# electronGPS.net
KiCad netlist of a schematic drawn in EAGLE
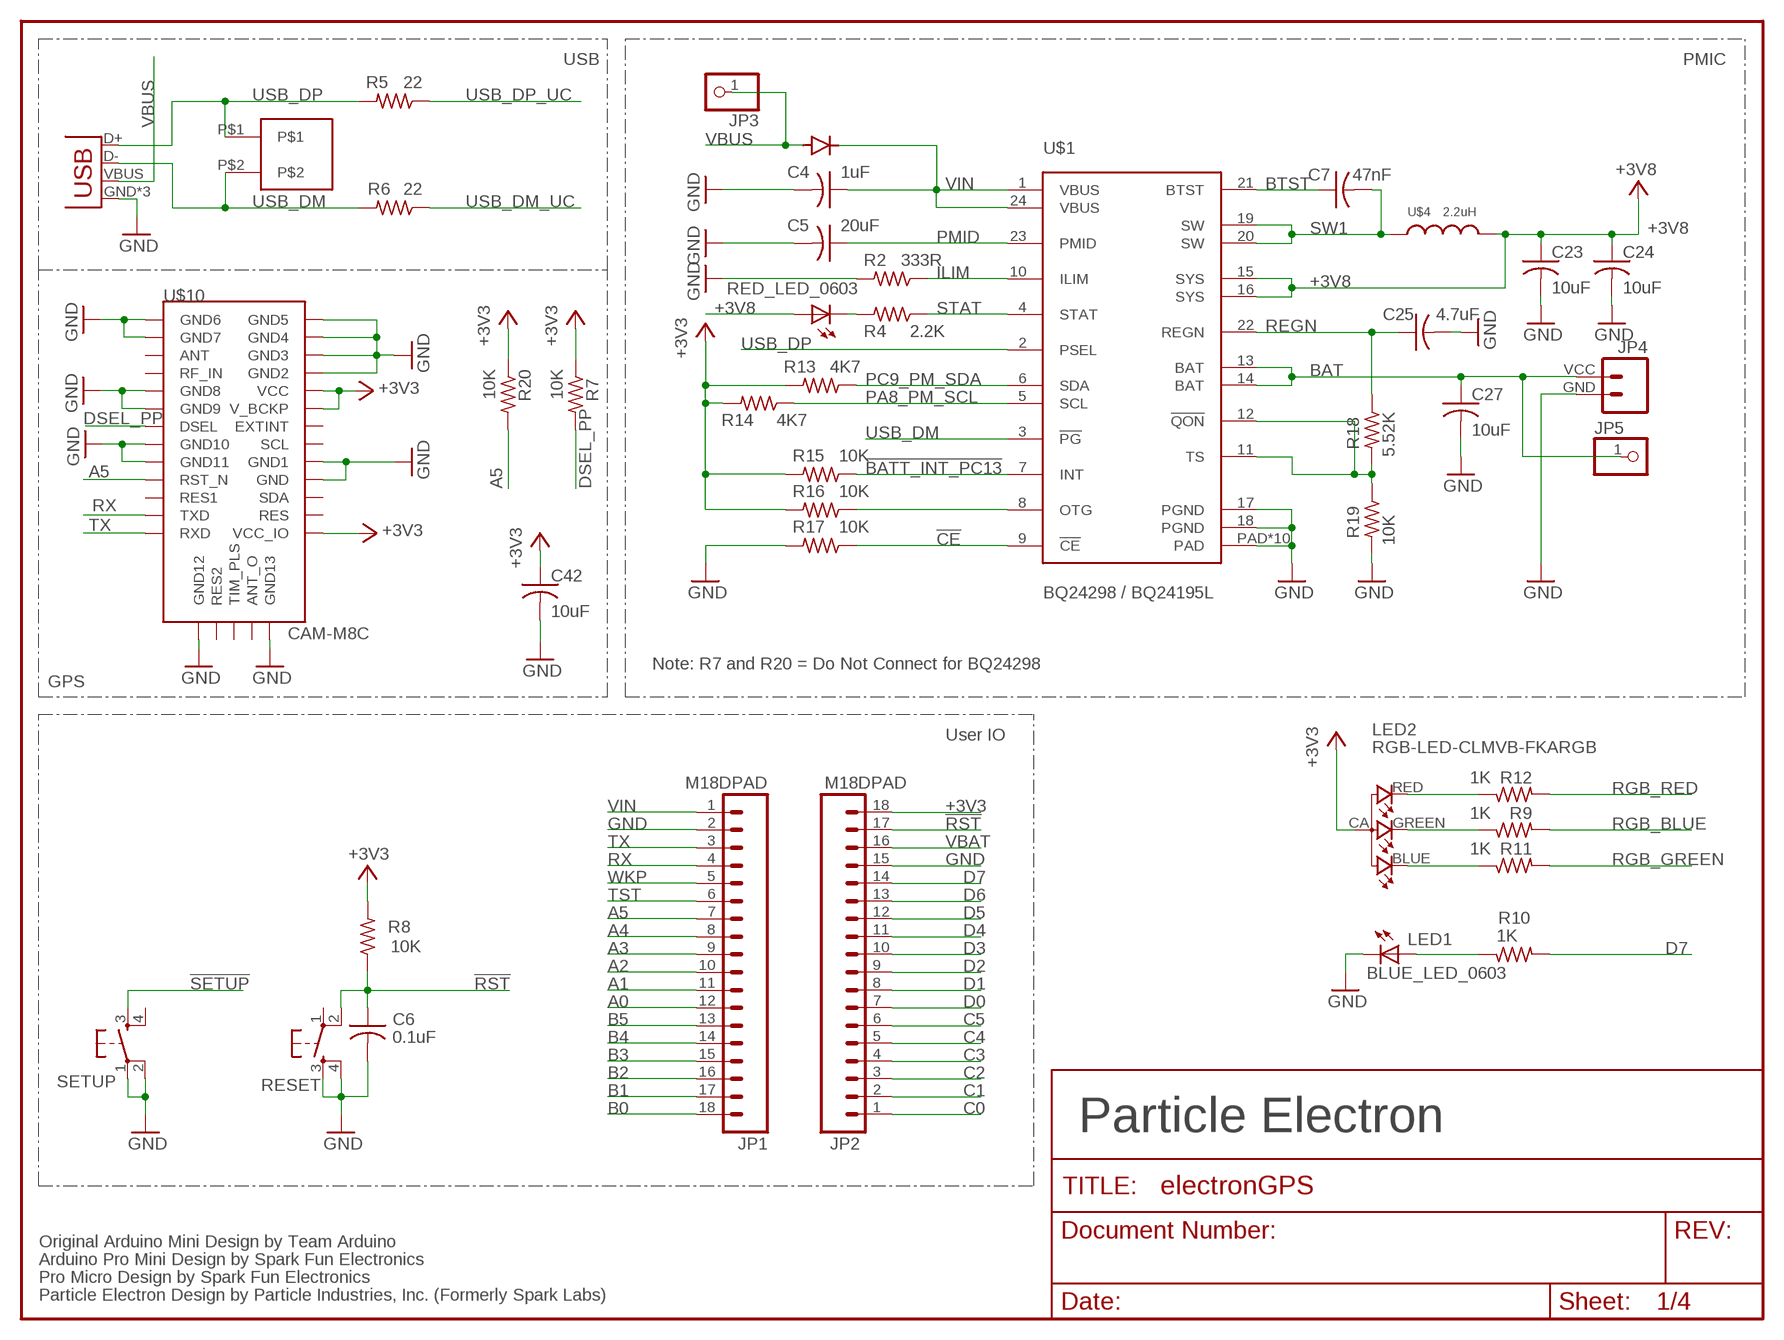
[diagram p0: schematic, sheet 1]
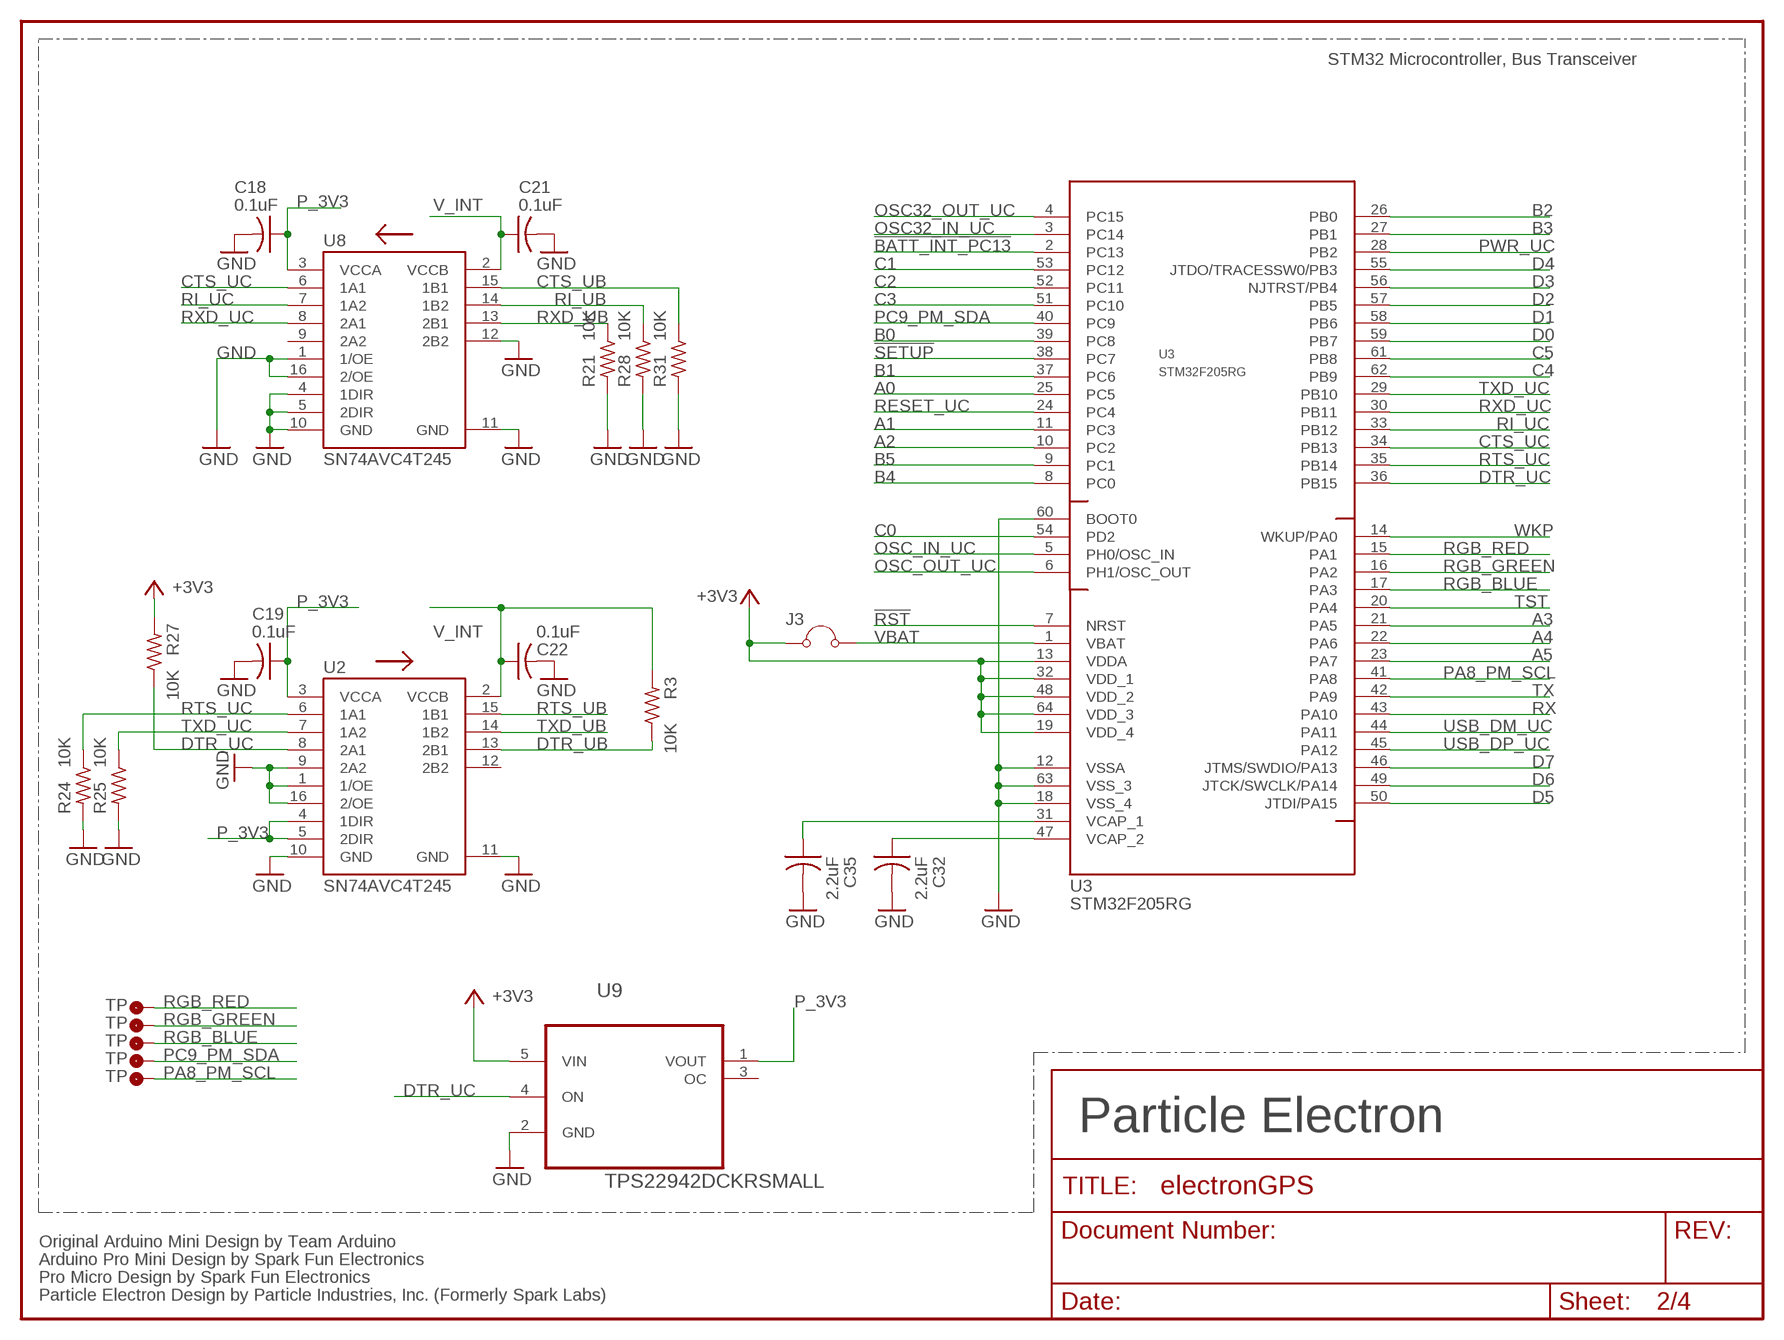
[diagram p1: schematic, sheet 2]
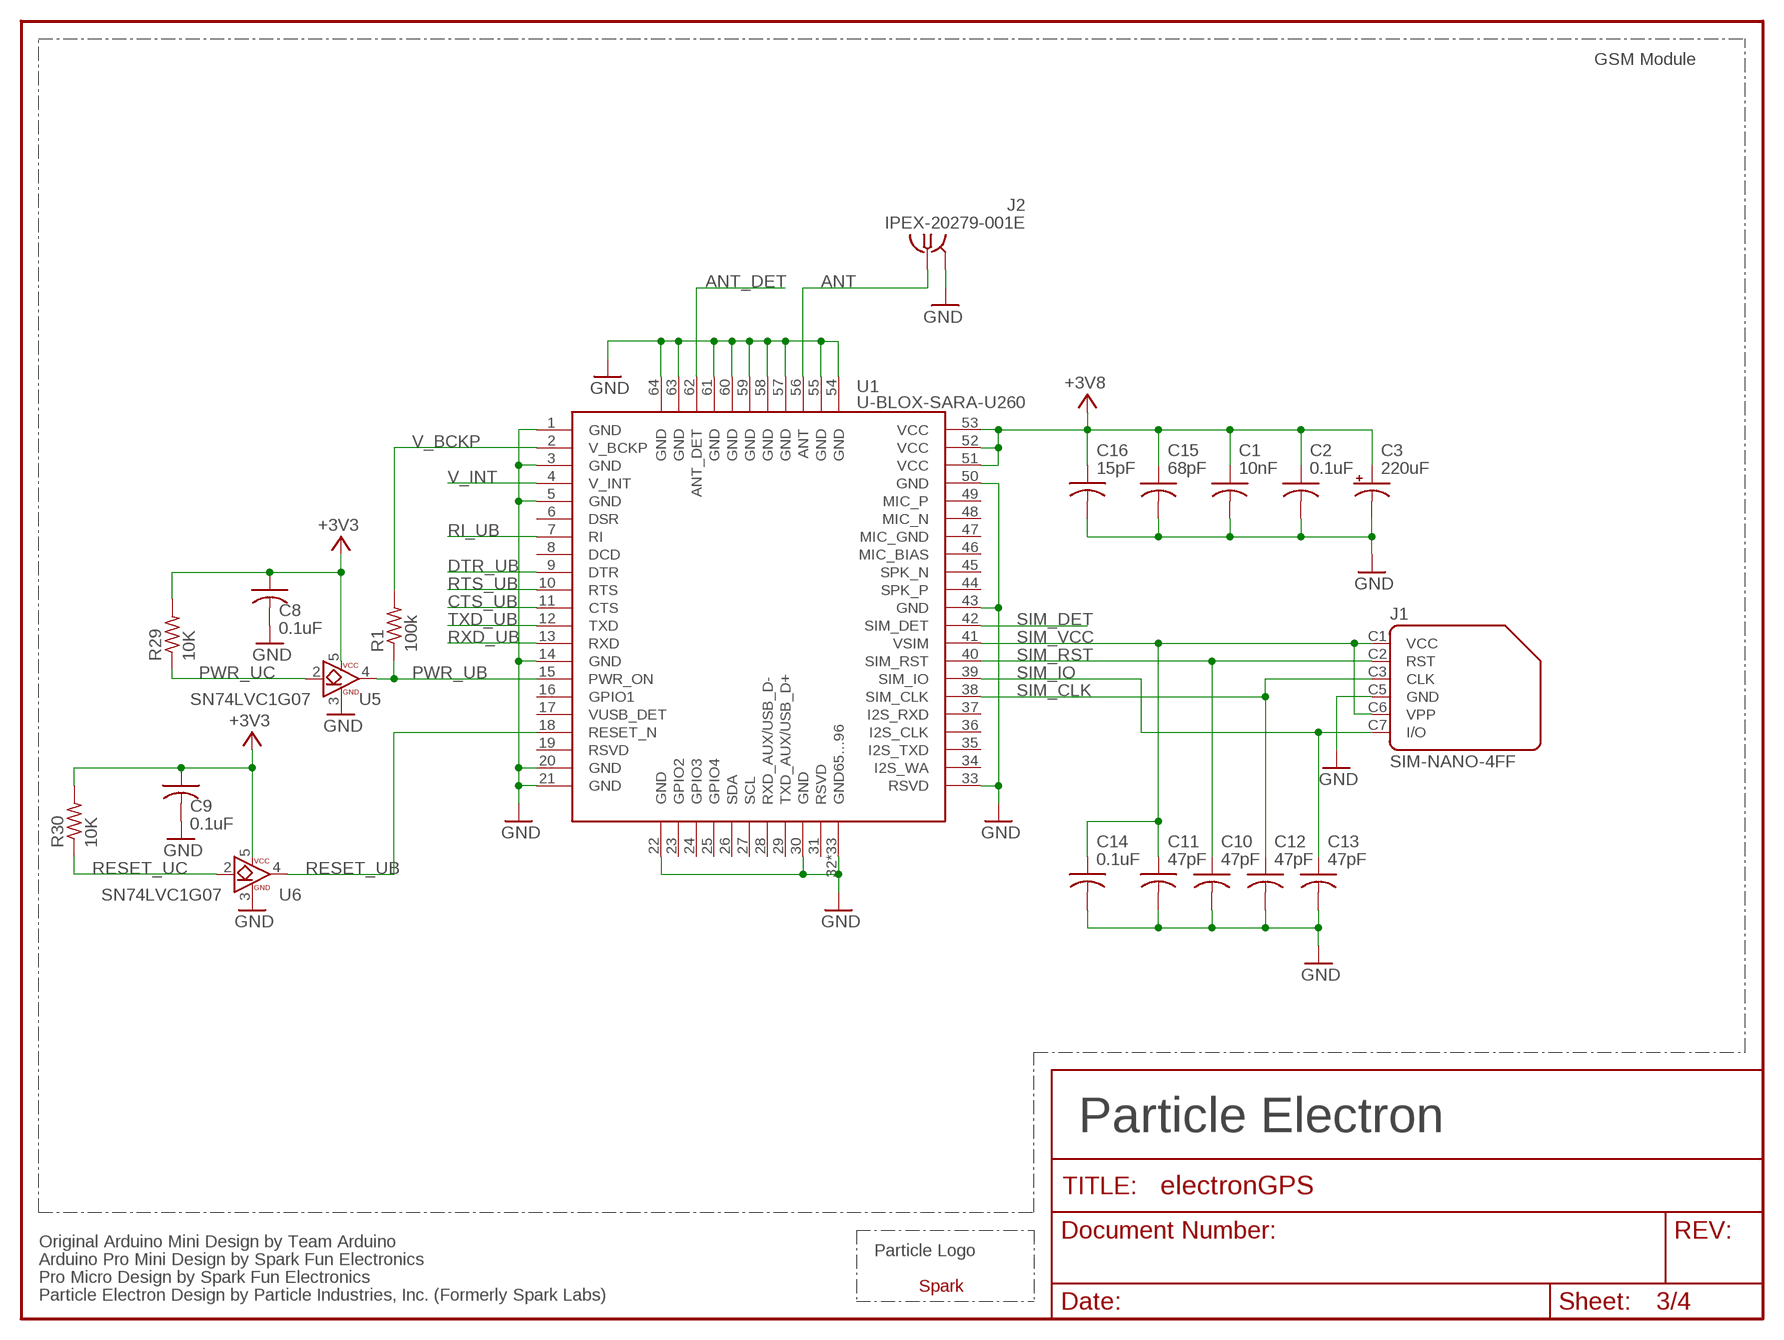
[diagram p2: schematic, sheet 3]
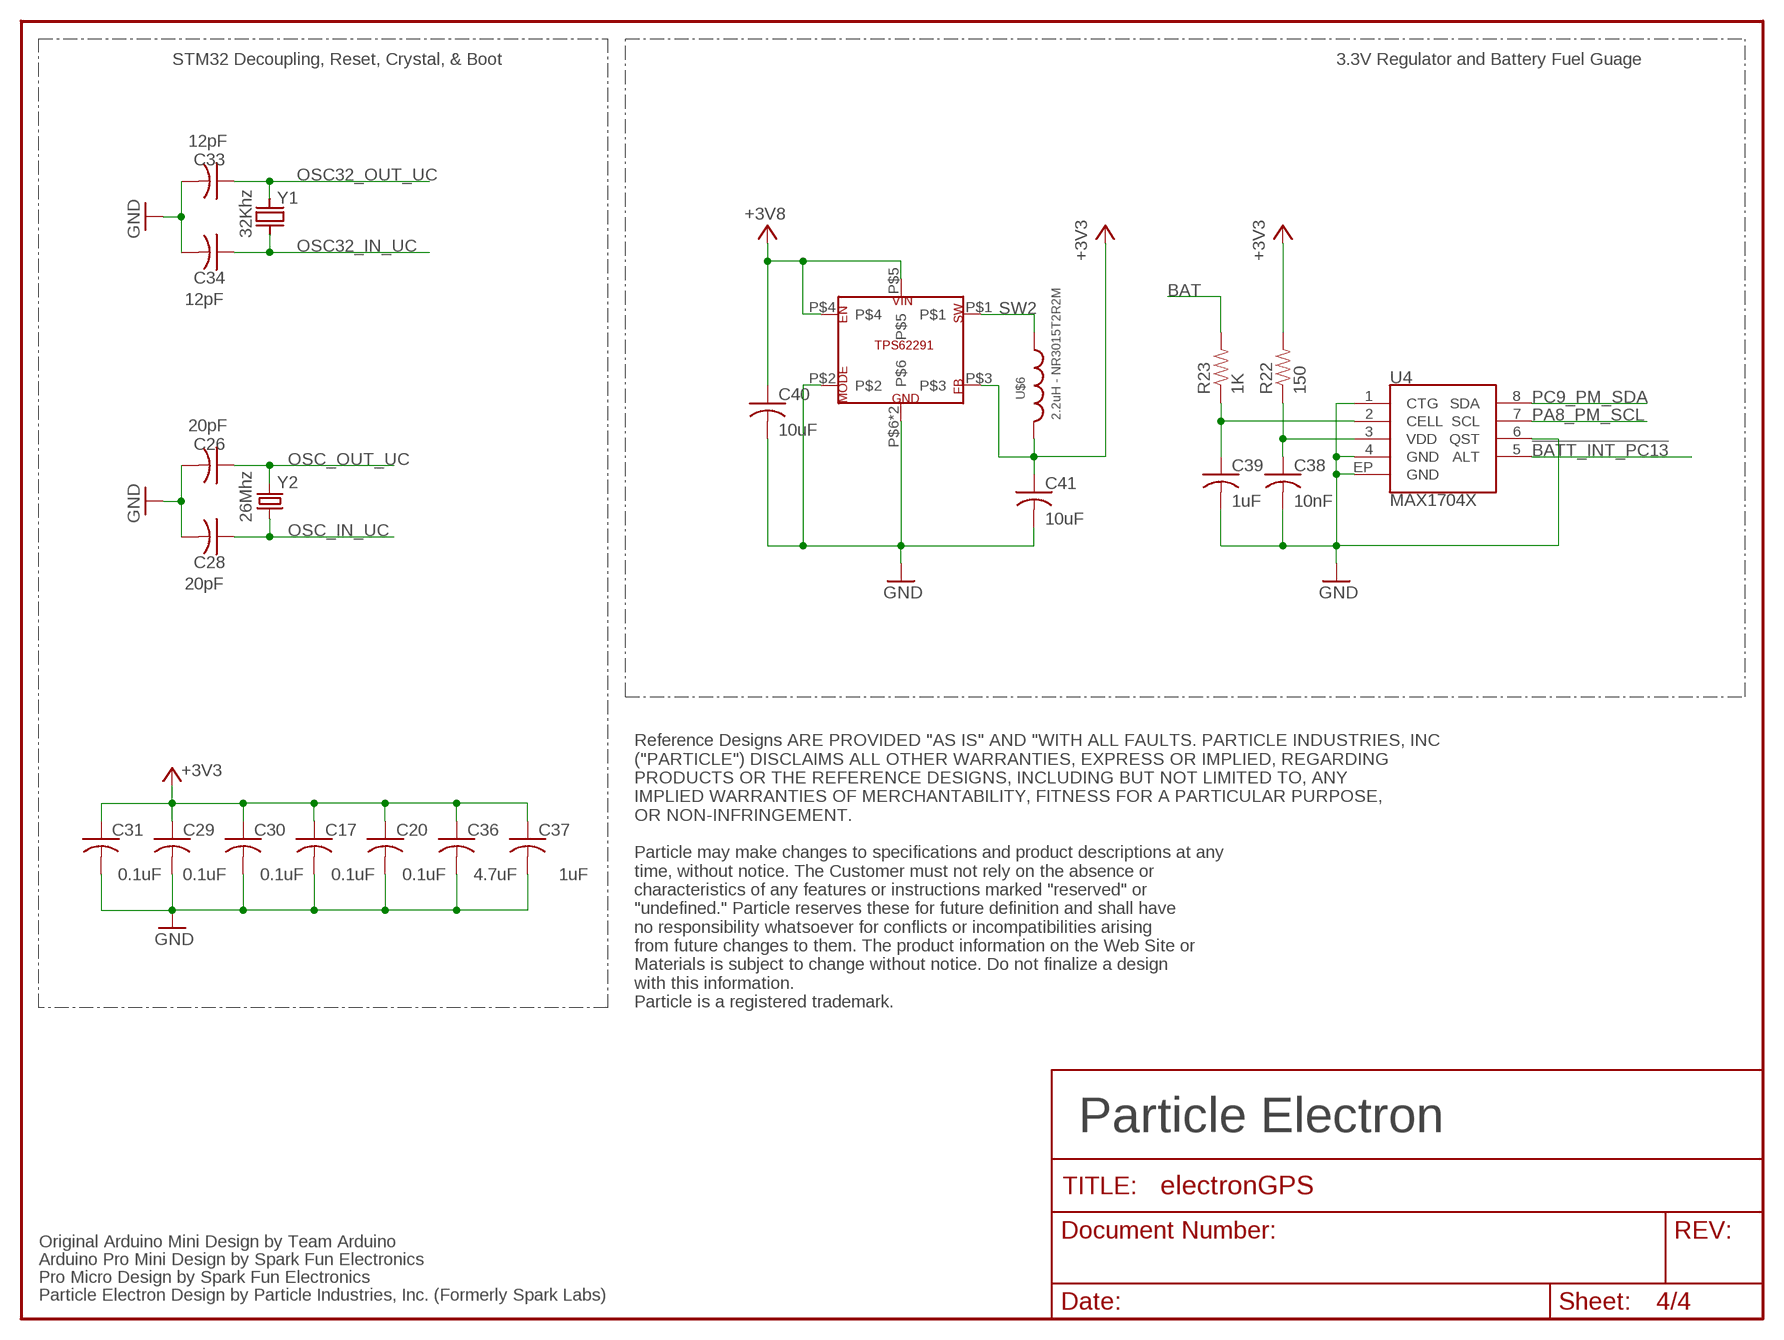
[diagram p3: schematic, sheet 4]

(export (version "E")
  (design (tool "Eeschema 10.0.6"))
  (components
    (comp (ref "C18")
      (value "0.1uF")
      (footprint "eagle-import:C0402_B")
      (libsource (lib "eagle-import") (part "C-US"))
    )
    (comp (ref "C19")
      (value "0.1uF")
      (footprint "eagle-import:C0402_B")
      (libsource (lib "eagle-import") (part "C-US"))
    )
    (comp (ref "C21")
      (value "0.1uF")
      (footprint "eagle-import:C0402_B")
      (libsource (lib "eagle-import") (part "C-US"))
    )
    (comp (ref "C22")
      (value "0.1uF")
      (footprint "eagle-import:C0402_B")
      (libsource (lib "eagle-import") (part "C-US"))
    )
    (comp (ref "C32")
      (value "2.2uF")
      (footprint "eagle-import:C0402_B")
      (libsource (lib "eagle-import") (part "C-US"))
    )
    (comp (ref "C35")
      (value "2.2uF")
      (footprint "eagle-import:C0402_B")
      (libsource (lib "eagle-import") (part "C-US"))
    )
    (comp (ref "J3")
      (value "JUMPER_NC_SMD")
      (footprint "eagle-import:JUMPER_SMD_NC")
      (libsource (lib "eagle-import") (part "JUMPER_NC_SMD"))
    )
    (comp (ref "R3")
      (value "10K")
      (footprint "eagle-import:R0402_B")
      (libsource (lib "eagle-import") (part "R-US_"))
    )
    (comp (ref "R21")
      (value "10K")
      (footprint "eagle-import:R0402_B")
      (libsource (lib "eagle-import") (part "R-US_"))
    )
    (comp (ref "R24")
      (value "10K")
      (footprint "eagle-import:R0402_B")
      (libsource (lib "eagle-import") (part "R-US_"))
    )
    (comp (ref "R25")
      (value "10K")
      (footprint "eagle-import:R0402_B")
      (libsource (lib "eagle-import") (part "R-US_"))
    )
    (comp (ref "R27")
      (value "10K")
      (footprint "eagle-import:R0402_B")
      (libsource (lib "eagle-import") (part "R-US_"))
    )
    (comp (ref "R28")
      (value "10K")
      (footprint "eagle-import:R0402_B")
      (libsource (lib "eagle-import") (part "R-US_"))
    )
    (comp (ref "R31")
      (value "10K")
      (footprint "eagle-import:R0402_B")
      (libsource (lib "eagle-import") (part "R-US_"))
    )
    (comp (ref "U$8")
      (value "TP0")
      (footprint "eagle-import:TP30_BOT")
      (libsource (lib "eagle-import") (part "TP0"))
    )
    (comp (ref "U$9")
      (value "TP0")
      (footprint "eagle-import:TP30_BOT")
      (libsource (lib "eagle-import") (part "TP0"))
    )
    (comp (ref "U$11")
      (value "TP0")
      (footprint "eagle-import:TP30_BOT")
      (libsource (lib "eagle-import") (part "TP0"))
    )
    (comp (ref "U$12")
      (value "TP0")
      (footprint "eagle-import:TP30_BOT")
      (libsource (lib "eagle-import") (part "TP0"))
    )
    (comp (ref "U$13")
      (value "TP0")
      (footprint "eagle-import:TP30_BOT")
      (libsource (lib "eagle-import") (part "TP0"))
    )
    (comp (ref "U2")
      (value "SN74AVC4T245")
      (footprint "eagle-import:UFQFN-16")
      (libsource (lib "eagle-import") (part "SN74AVC4T245"))
    )
    (comp (ref "U3")
      (value "STM32F205RG")
      (footprint "eagle-import:LQFP64")
      (libsource (lib "eagle-import") (part "STM32F20XR"))
    )
    (comp (ref "U8")
      (value "SN74AVC4T245")
      (footprint "eagle-import:UFQFN-16")
      (libsource (lib "eagle-import") (part "SN74AVC4T245"))
    )
    (comp (ref "U9")
      (value "TPS22942DCKRSMALL")
      (footprint "eagle-import:SC70-5")
      (libsource (lib "eagle-import") (part "TPS22942DCKRSMALL"))
    )
    (comp (ref "BLUE_LED_0603")
      (value "LEDNOSILK")
      (footprint "eagle-import:LED-0603-NS")
      (libsource (lib "eagle-import") (part "LEDNOSILK"))
    )
    (comp (ref "C4")
      (value "1uF")
      (footprint "eagle-import:C0603_B")
      (libsource (lib "eagle-import") (part "C-US0603"))
    )
    (comp (ref "C5")
      (value "20uF")
      (footprint "eagle-import:C0603_B")
      (libsource (lib "eagle-import") (part "C-US0603"))
    )
    (comp (ref "C6")
      (value "0.1uF")
      (footprint "eagle-import:C0402_B")
      (libsource (lib "eagle-import") (part "C-US"))
    )
    (comp (ref "C7")
      (value "47nF")
      (footprint "eagle-import:C0402_B")
      (libsource (lib "eagle-import") (part "C-US"))
    )
    (comp (ref "C23")
      (value "10uF")
      (footprint "eagle-import:C0603_B")
      (libsource (lib "eagle-import") (part "C-US0603"))
    )
    (comp (ref "C24")
      (value "10uF")
      (footprint "eagle-import:C0603_B")
      (libsource (lib "eagle-import") (part "C-US0603"))
    )
    (comp (ref "C25")
      (value "4.7uF")
      (footprint "eagle-import:C0603_B")
      (libsource (lib "eagle-import") (part "C-US0603"))
    )
    (comp (ref "C27")
      (value "10uF")
      (footprint "eagle-import:C0603_B")
      (libsource (lib "eagle-import") (part "C-US0603"))
    )
    (comp (ref "C42")
      (value "10uF")
      (footprint "eagle-import:C0603_B")
      (libsource (lib "eagle-import") (part "C-US0603"))
    )
    (comp (ref "JP1")
      (value "M18DPAD")
      (footprint "eagle-import:1X18-D-PADS")
      (libsource (lib "eagle-import") (part "M18DPAD"))
    )
    (comp (ref "JP2")
      (value "M18DPAD")
      (footprint "eagle-import:1X18-D-PADS")
      (libsource (lib "eagle-import") (part "M18DPAD"))
    )
    (comp (ref "JP3")
      (value "PINHD-1X1NOSILK")
      (footprint "eagle-import:1X01_NO_SILK")
      (libsource (lib "eagle-import") (part "PINHD-1X1NOSILK"))
    )
    (comp (ref "JP4")
      (value "M024UCON-15767")
      (footprint "eagle-import:JST-2-SMD-VERT")
      (libsource (lib "eagle-import") (part "M024UCON-15767"))
    )
    (comp (ref "JP5")
      (value "PINHD-1X1NOSILK")
      (footprint "eagle-import:1X01_NO_SILK")
      (libsource (lib "eagle-import") (part "PINHD-1X1NOSILK"))
    )
    (comp (ref "LED2")
      (value "RGB-LED-CLMVB-FKARGB")
      (footprint "eagle-import:PLCC4-2MM-RGB")
      (libsource (lib "eagle-import") (part "RGB-LED-CLMVB-FKARGB"))
    )
    (comp (ref "R2")
      (value "333R")
      (footprint "eagle-import:R0402_B")
      (libsource (lib "eagle-import") (part "R-US_"))
    )
    (comp (ref "R4")
      (value "2.2K")
      (footprint "eagle-import:R0402_B")
      (libsource (lib "eagle-import") (part "R-US_"))
    )
    (comp (ref "R5")
      (value "22")
      (footprint "eagle-import:R0402_B")
      (libsource (lib "eagle-import") (part "R-US_"))
    )
    (comp (ref "R6")
      (value "22")
      (footprint "eagle-import:R0402_B")
      (libsource (lib "eagle-import") (part "R-US_"))
    )
    (comp (ref "R7")
      (value "10K")
      (footprint "eagle-import:R0402_B")
      (libsource (lib "eagle-import") (part "R-US_"))
    )
    (comp (ref "R8")
      (value "10K")
      (footprint "eagle-import:R0402_B")
      (libsource (lib "eagle-import") (part "R-US_"))
    )
    (comp (ref "R9")
      (value "1K")
      (footprint "eagle-import:R0402_B")
      (libsource (lib "eagle-import") (part "R-US_"))
    )
    (comp (ref "R10")
      (value "1K")
      (footprint "eagle-import:R0402_B")
      (libsource (lib "eagle-import") (part "R-US_"))
    )
    (comp (ref "R11")
      (value "1K")
      (footprint "eagle-import:R0402_B")
      (libsource (lib "eagle-import") (part "R-US_"))
    )
    (comp (ref "R12")
      (value "1K")
      (footprint "eagle-import:R0402_B")
      (libsource (lib "eagle-import") (part "R-US_"))
    )
    (comp (ref "R13")
      (value "4K7")
      (footprint "eagle-import:R0402_B")
      (libsource (lib "eagle-import") (part "R-US_"))
    )
    (comp (ref "R14")
      (value "4K7")
      (footprint "eagle-import:R0402_B")
      (libsource (lib "eagle-import") (part "R-US_"))
    )
    (comp (ref "R15")
      (value "10K")
      (footprint "eagle-import:R0402_B")
      (libsource (lib "eagle-import") (part "R-US_"))
    )
    (comp (ref "R16")
      (value "10K")
      (footprint "eagle-import:R0402_B")
      (libsource (lib "eagle-import") (part "R-US_"))
    )
    (comp (ref "R17")
      (value "10K")
      (footprint "eagle-import:R0402_B")
      (libsource (lib "eagle-import") (part "R-US_"))
    )
    (comp (ref "R18")
      (value "5.52K")
      (footprint "eagle-import:R0402_B")
      (libsource (lib "eagle-import") (part "R-US_"))
    )
    (comp (ref "R19")
      (value "10K")
      (footprint "eagle-import:R0402_B")
      (libsource (lib "eagle-import") (part "R-US_"))
    )
    (comp (ref "R20")
      (value "10K")
      (footprint "eagle-import:R0402_B")
      (libsource (lib "eagle-import") (part "R-US_"))
    )
    (comp (ref "RED_LED_0603")
      (value "LED0603")
      (footprint "eagle-import:LED-0603")
      (libsource (lib "eagle-import") (part "LED0603"))
    )
    (comp (ref "RESET")
      (value "KMR211GLFS")
      (footprint "eagle-import:TACTILE_SWITCH_SMD")
      (libsource (lib "eagle-import") (part "TAC_SWITCHSMD"))
    )
    (comp (ref "SETUP")
      (value "KMR211GLFS")
      (footprint "eagle-import:TACTILE_SWITCH_SMD")
      (libsource (lib "eagle-import") (part "TAC_SWITCHSMD"))
    )
    (comp (ref "U$1")
      (value "BQ24298 / BQ24195L")
      (footprint "eagle-import:QFN24")
      (libsource (lib "eagle-import") (part "BQ24298RTWR"))
    )
    (comp (ref "U$3")
      (value "DIODE_NT")
      (footprint "eagle-import:DIODE-DO-220AA_NT(SMP)")
      (libsource (lib "eagle-import") (part "DIODE_NT"))
    )
    (comp (ref "U$4")
      (value "2.2uH")
      (footprint "eagle-import:4020TYPE_NT")
      (libsource (lib "eagle-import") (part "INDUCTOR_NT"))
    )
    (comp (ref "U$7")
      (value "M02_0.05_HEADER")
      (footprint "eagle-import:M02_0.05_HEADER")
      (libsource (lib "eagle-import") (part "M02_0.05_HEADER"))
    )
    (comp (ref "U$10")
      (value "CAM-M8C")
      (footprint "eagle-import:CAM-MC")
      (libsource (lib "eagle-import") (part "CAM-M8C"))
    )
    (comp (ref "X1")
      (value "USB-MICROB")
      (footprint "eagle-import:USB-MICROB-SLOT-HOLE")
      (libsource (lib "eagle-import") (part "USBUSB-MICROB-SLOT-HOLE"))
    )
    (comp (ref "C1")
      (value "10nF")
      (footprint "eagle-import:C0402_B")
      (libsource (lib "eagle-import") (part "C-US"))
    )
    (comp (ref "C2")
      (value "0.1uF")
      (footprint "eagle-import:C0402_B")
      (libsource (lib "eagle-import") (part "C-US"))
    )
    (comp (ref "C3")
      (value "220uF")
      (footprint "eagle-import:C_6032-28R")
      (libsource (lib "eagle-import") (part "CPOL-USC/6032-28R"))
    )
    (comp (ref "C8")
      (value "0.1uF")
      (footprint "eagle-import:C0402_B")
      (libsource (lib "eagle-import") (part "C-US"))
    )
    (comp (ref "C9")
      (value "0.1uF")
      (footprint "eagle-import:C0402_B")
      (libsource (lib "eagle-import") (part "C-US"))
    )
    (comp (ref "C10")
      (value "47pF")
      (footprint "eagle-import:C0402_B")
      (libsource (lib "eagle-import") (part "C-US"))
    )
    (comp (ref "C11")
      (value "47pF")
      (footprint "eagle-import:C0402_B")
      (libsource (lib "eagle-import") (part "C-US"))
    )
    (comp (ref "C12")
      (value "47pF")
      (footprint "eagle-import:C0402_B")
      (libsource (lib "eagle-import") (part "C-US"))
    )
    (comp (ref "C13")
      (value "47pF")
      (footprint "eagle-import:C0402_B")
      (libsource (lib "eagle-import") (part "C-US"))
    )
    (comp (ref "C14")
      (value "0.1uF")
      (footprint "eagle-import:C0402_B")
      (libsource (lib "eagle-import") (part "C-US"))
    )
    (comp (ref "C15")
      (value "68pF")
      (footprint "eagle-import:C0402_B")
      (libsource (lib "eagle-import") (part "C-US"))
    )
    (comp (ref "C16")
      (value "15pF")
      (footprint "eagle-import:C0402_B")
      (libsource (lib "eagle-import") (part "C-US"))
    )
    (comp (ref "J1")
      (value "SIM-NANO-4FF")
      (footprint "eagle-import:GCT-SIM8100")
      (libsource (lib "eagle-import") (part "SIM-NANO-4FF"))
    )
    (comp (ref "J2")
      (value "IPEX-20279-001E")
      (footprint "eagle-import:IPEX-20279-001E")
      (libsource (lib "eagle-import") (part "IPEX-20279-001E"))
    )
    (comp (ref "R1")
      (value "100k")
      (footprint "eagle-import:R0402_B")
      (libsource (lib "eagle-import") (part "R-US_"))
    )
    (comp (ref "R29")
      (value "10K")
      (footprint "eagle-import:R0402_B")
      (libsource (lib "eagle-import") (part "R-US_"))
    )
    (comp (ref "R30")
      (value "10K")
      (footprint "eagle-import:R0402_B")
      (libsource (lib "eagle-import") (part "R-US_"))
    )
    (comp (ref "U$2")
      (value "SPARK_LOGO2")
      (footprint "eagle-import:SPARK_LOGO2")
      (libsource (lib "eagle-import") (part "SPARK_LOGO2"))
    )
    (comp (ref "U1")
      (value "U-BLOX-SARA-U260")
      (footprint "eagle-import:U-BLOX-SARA-U2")
      (libsource (lib "eagle-import") (part "U-BLOX-SARA-U260"))
    )
    (comp (ref "U5")
      (value "SN74LVC1G07")
      (footprint "eagle-import:SC-70-5")
      (libsource (lib "eagle-import") (part "SN74LVC1G07"))
    )
    (comp (ref "U6")
      (value "SN74LVC1G07")
      (footprint "eagle-import:SC-70-5")
      (libsource (lib "eagle-import") (part "SN74LVC1G07"))
    )
    (comp (ref "C17")
      (value "0.1uF")
      (footprint "eagle-import:C0402_B")
      (libsource (lib "eagle-import") (part "C-US"))
    )
    (comp (ref "C20")
      (value "0.1uF")
      (footprint "eagle-import:C0402_B")
      (libsource (lib "eagle-import") (part "C-US"))
    )
    (comp (ref "C26")
      (value "20pF")
      (footprint "eagle-import:C0402_B")
      (libsource (lib "eagle-import") (part "C-US"))
    )
    (comp (ref "C28")
      (value "20pF")
      (footprint "eagle-import:C0402_B")
      (libsource (lib "eagle-import") (part "C-US"))
    )
    (comp (ref "C29")
      (value "0.1uF")
      (footprint "eagle-import:C0402_B")
      (libsource (lib "eagle-import") (part "C-US"))
    )
    (comp (ref "C30")
      (value "0.1uF")
      (footprint "eagle-import:C0402_B")
      (libsource (lib "eagle-import") (part "C-US"))
    )
    (comp (ref "C31")
      (value "0.1uF")
      (footprint "eagle-import:C0402_B")
      (libsource (lib "eagle-import") (part "C-US"))
    )
    (comp (ref "C33")
      (value "12pF")
      (footprint "eagle-import:C0402_B")
      (libsource (lib "eagle-import") (part "C-US"))
    )
    (comp (ref "C34")
      (value "12pF")
      (footprint "eagle-import:C0402_B")
      (libsource (lib "eagle-import") (part "C-US"))
    )
    (comp (ref "C36")
      (value "4.7uF")
      (footprint "eagle-import:C0402_B")
      (libsource (lib "eagle-import") (part "C-US"))
    )
    (comp (ref "C37")
      (value "1uF")
      (footprint "eagle-import:C0402_B")
      (libsource (lib "eagle-import") (part "C-US"))
    )
    (comp (ref "C38")
      (value "10nF")
      (footprint "eagle-import:C0402_B")
      (libsource (lib "eagle-import") (part "C-US"))
    )
    (comp (ref "C39")
      (value "1uF")
      (footprint "eagle-import:C0402_B")
      (libsource (lib "eagle-import") (part "C-US"))
    )
    (comp (ref "C40")
      (value "10uF")
      (footprint "eagle-import:C0603_B")
      (libsource (lib "eagle-import") (part "C-US0603"))
    )
    (comp (ref "C41")
      (value "10uF")
      (footprint "eagle-import:C0603_B")
      (libsource (lib "eagle-import") (part "C-US0603"))
    )
    (comp (ref "R22")
      (value "150")
      (footprint "eagle-import:0603-RES")
      (libsource (lib "eagle-import") (part "RESISTOR0603-RES"))
    )
    (comp (ref "R23")
      (value "1K")
      (footprint "eagle-import:0603-RES")
      (libsource (lib "eagle-import") (part "RESISTOR0603-RES"))
    )
    (comp (ref "U$5")
      (value "TPS62291DRV")
      (footprint "eagle-import:S-PWSON-N6")
      (libsource (lib "eagle-import") (part "TPS62291DRV"))
    )
    (comp (ref "U$6")
      (value "2.2uH - NR3015T2R2M")
      (footprint "eagle-import:INDUCTOR-NR3015")
      (libsource (lib "eagle-import") (part "INDUCTORB"))
    )
    (comp (ref "U4")
      (value "MAX1704X")
      (footprint "eagle-import:TDFN-8")
      (libsource (lib "eagle-import") (part "MAX1704X"))
    )
    (comp (ref "Y1")
      (value "32Khz")
      (footprint "eagle-import:FC135")
      (libsource (lib "eagle-import") (part "Q_FC135"))
    )
    (comp (ref "Y2")
      (value "26Mhz")
      (footprint "eagle-import:CRYSTAL-SMD-5X3")
      (libsource (lib "eagle-import") (part "CRYSTAL5X3"))
    )
  )
  (nets
    (net (code "1") (name "+3V3") (class "Default")
      (node (ref "C17") (pin "1") (pinfunction "1_1") (pintype "passive"))
      (node (ref "C20") (pin "1") (pinfunction "1_1") (pintype "passive"))
      (node (ref "C29") (pin "1") (pinfunction "1_1") (pintype "passive"))
      (node (ref "C30") (pin "1") (pinfunction "1_1") (pintype "passive"))
      (node (ref "C31") (pin "1") (pinfunction "1_1") (pintype "passive"))
      (node (ref "C36") (pin "1") (pinfunction "1_1") (pintype "passive"))
      (node (ref "C37") (pin "1") (pinfunction "1_1") (pintype "passive"))
      (node (ref "C41") (pin "1") (pinfunction "1_1") (pintype "passive"))
      (node (ref "C42") (pin "1") (pinfunction "1_1") (pintype "passive"))
      (node (ref "C8") (pin "1") (pinfunction "1_1") (pintype "passive"))
      (node (ref "C9") (pin "1") (pinfunction "1_1") (pintype "passive"))
      (node (ref "J3") (pin "1") (pinfunction "1_1") (pintype "bidirectional"))
      (node (ref "JP2") (pin "18") (pinfunction "18_18") (pintype "passive"))
      (node (ref "LED2") (pin "CA") (pinfunction "1_CA") (pintype "passive"))
      (node (ref "R13") (pin "2") (pinfunction "2_2") (pintype "passive"))
      (node (ref "R14") (pin "2") (pinfunction "2_2") (pintype "passive"))
      (node (ref "R15") (pin "2") (pinfunction "2_2") (pintype "passive"))
      (node (ref "R16") (pin "2") (pinfunction "2_2") (pintype "passive"))
      (node (ref "R20") (pin "1") (pinfunction "1_1") (pintype "passive"))
      (node (ref "R22") (pin "2") (pinfunction "2_2") (pintype "passive"))
      (node (ref "R27") (pin "2") (pinfunction "2_2") (pintype "passive"))
      (node (ref "R29") (pin "2") (pinfunction "2_2") (pintype "passive"))
      (node (ref "R30") (pin "2") (pinfunction "2_2") (pintype "passive"))
      (node (ref "R7") (pin "1") (pinfunction "1_1") (pintype "passive"))
      (node (ref "R8") (pin "2") (pinfunction "2_2") (pintype "passive"))
      (node (ref "U$10") (pin "P$1") (pinfunction "VCC_IO_P$1") (pintype "bidirectional"))
      (node (ref "U$10") (pin "P$8") (pinfunction "V_BCKP_P$8") (pintype "bidirectional"))
      (node (ref "U$10") (pin "P$9") (pinfunction "VCC_P$9") (pintype "bidirectional"))
      (node (ref "U$5") (pin "P$3") (pinfunction "P$3_P$3") (pintype "bidirectional"))
      (node (ref "U$6") (pin "2") (pinfunction "2_2") (pintype "passive"))
      (node (ref "U3") (pin "13") (pinfunction "VDDA_13") (pintype "power_in"))
      (node (ref "U3") (pin "19") (pinfunction "VDD_4_19") (pintype "power_in"))
      (node (ref "U3") (pin "32") (pinfunction "VDD_1_32") (pintype "power_in"))
      (node (ref "U3") (pin "48") (pinfunction "VDD_2_48") (pintype "power_in"))
      (node (ref "U3") (pin "64") (pinfunction "VDD_3_64") (pintype "power_in"))
      (node (ref "U5") (pin "5") (pinfunction "VCC_5") (pintype "bidirectional"))
      (node (ref "U6") (pin "5") (pinfunction "VCC_5") (pintype "bidirectional"))
      (node (ref "U9") (pin "5") (pinfunction "VIN_5") (pintype "power_in"))
    )
    (net (code "2") (name "+3V8") (class "Default")
      (node (ref "C1") (pin "1") (pinfunction "1_1") (pintype "passive"))
      (node (ref "C15") (pin "1") (pinfunction "1_1") (pintype "passive"))
      (node (ref "C16") (pin "1") (pinfunction "1_1") (pintype "passive"))
      (node (ref "C2") (pin "1") (pinfunction "1_1") (pintype "passive"))
      (node (ref "C23") (pin "1") (pinfunction "1_1") (pintype "passive"))
      (node (ref "C24") (pin "1") (pinfunction "1_1") (pintype "passive"))
      (node (ref "C3") (pin "+") (pinfunction "+_+") (pintype "passive"))
      (node (ref "C40") (pin "1") (pinfunction "1_1") (pintype "passive"))
      (node (ref "RED_LED_0603") (pin "A") (pinfunction "A_A") (pintype "passive"))
      (node (ref "U$1") (pin "15") (pinfunction "SYS_15") (pintype "power_in"))
      (node (ref "U$1") (pin "16") (pinfunction "SYS_16") (pintype "power_in"))
      (node (ref "U$4") (pin "P$2") (pinfunction "2_P$2") (pintype "passive"))
      (node (ref "U$5") (pin "P$4") (pinfunction "P$4_P$4") (pintype "bidirectional"))
      (node (ref "U$5") (pin "P$5") (pinfunction "P$5_P$5") (pintype "bidirectional"))
      (node (ref "U1") (pin "51") (pinfunction "VCC_51") (pintype "bidirectional"))
      (node (ref "U1") (pin "52") (pinfunction "VCC_52") (pintype "bidirectional"))
      (node (ref "U1") (pin "53") (pinfunction "VCC_53") (pintype "bidirectional"))
    )
    (net (code "3") (name "A0") (class "Default")
      (node (ref "JP1") (pin "12") (pinfunction "12_12") (pintype "passive"))
      (node (ref "U3") (pin "25") (pinfunction "PC5_25") (pintype "bidirectional"))
    )
    (net (code "4") (name "A1") (class "Default")
      (node (ref "JP1") (pin "11") (pinfunction "11_11") (pintype "passive"))
      (node (ref "U3") (pin "11") (pinfunction "PC3_11") (pintype "bidirectional"))
    )
    (net (code "5") (name "A2") (class "Default")
      (node (ref "JP1") (pin "10") (pinfunction "10_10") (pintype "passive"))
      (node (ref "U3") (pin "10") (pinfunction "PC2_10") (pintype "bidirectional"))
    )
    (net (code "6") (name "A3") (class "Default")
      (node (ref "JP1") (pin "9") (pinfunction "9_9") (pintype "passive"))
      (node (ref "U3") (pin "21") (pinfunction "PA5_21") (pintype "bidirectional"))
    )
    (net (code "7") (name "A4") (class "Default")
      (node (ref "JP1") (pin "8") (pinfunction "8_8") (pintype "passive"))
      (node (ref "U3") (pin "22") (pinfunction "PA6_22") (pintype "bidirectional"))
    )
    (net (code "8") (name "A5") (class "Default")
      (node (ref "JP1") (pin "7") (pinfunction "7_7") (pintype "passive"))
      (node (ref "R20") (pin "2") (pinfunction "2_2") (pintype "passive"))
      (node (ref "U$10") (pin "P$23") (pinfunction "RST_N_P$23") (pintype "bidirectional"))
      (node (ref "U3") (pin "23") (pinfunction "PA7_23") (pintype "bidirectional"))
    )
    (net (code "9") (name "ANT") (class "Default")
      (node (ref "J2") (pin "1") (pinfunction "1_1") (pintype "passive"))
      (node (ref "U1") (pin "56") (pinfunction "ANT_56") (pintype "bidirectional"))
    )
    (net (code "10") (name "ANT_DET") (class "Default")
      (node (ref "U1") (pin "62") (pinfunction "ANT_DET_62") (pintype "bidirectional"))
    )
    (net (code "11") (name "B0") (class "Default")
      (node (ref "JP1") (pin "18") (pinfunction "18_18") (pintype "passive"))
      (node (ref "U3") (pin "39") (pinfunction "PC8_39") (pintype "bidirectional"))
    )
    (net (code "12") (name "B1") (class "Default")
      (node (ref "JP1") (pin "17") (pinfunction "17_17") (pintype "passive"))
      (node (ref "U3") (pin "37") (pinfunction "PC6_37") (pintype "bidirectional"))
    )
    (net (code "13") (name "B2") (class "Default")
      (node (ref "JP1") (pin "16") (pinfunction "16_16") (pintype "passive"))
      (node (ref "U3") (pin "26") (pinfunction "PB0_26") (pintype "bidirectional"))
    )
    (net (code "14") (name "B3") (class "Default")
      (node (ref "JP1") (pin "15") (pinfunction "15_15") (pintype "passive"))
      (node (ref "U3") (pin "27") (pinfunction "PB1_27") (pintype "bidirectional"))
    )
    (net (code "15") (name "B4") (class "Default")
      (node (ref "JP1") (pin "14") (pinfunction "14_14") (pintype "passive"))
      (node (ref "U3") (pin "8") (pinfunction "PC0_8") (pintype "bidirectional"))
    )
    (net (code "16") (name "B5") (class "Default")
      (node (ref "JP1") (pin "13") (pinfunction "13_13") (pintype "passive"))
      (node (ref "U3") (pin "9") (pinfunction "PC1_9") (pintype "bidirectional"))
    )
    (net (code "17") (name "BAT") (class "Default")
      (node (ref "C27") (pin "1") (pinfunction "1_1") (pintype "passive"))
      (node (ref "JP4") (pin "VCC") (pinfunction "2_VCC") (pintype "passive"))
      (node (ref "JP5") (pin "1") (pinfunction "1_1") (pintype "passive"))
      (node (ref "R23") (pin "2") (pinfunction "2_2") (pintype "passive"))
      (node (ref "U$1") (pin "13") (pinfunction "BAT_13") (pintype "passive"))
      (node (ref "U$1") (pin "14") (pinfunction "BAT_14") (pintype "power_in"))
    )
    (net (code "18") (name "BTST") (class "Default")
      (node (ref "C7") (pin "1") (pinfunction "1_1") (pintype "passive"))
      (node (ref "U$1") (pin "21") (pinfunction "BTST_21") (pintype "bidirectional"))
    )
    (net (code "19") (name "C0") (class "Default")
      (node (ref "JP2") (pin "1") (pinfunction "1_1") (pintype "passive"))
      (node (ref "U3") (pin "54") (pinfunction "PD2_54") (pintype "bidirectional"))
    )
    (net (code "20") (name "C1") (class "Default")
      (node (ref "JP2") (pin "2") (pinfunction "2_2") (pintype "passive"))
      (node (ref "U3") (pin "53") (pinfunction "PC12_53") (pintype "bidirectional"))
    )
    (net (code "21") (name "C2") (class "Default")
      (node (ref "JP2") (pin "3") (pinfunction "3_3") (pintype "passive"))
      (node (ref "U3") (pin "52") (pinfunction "PC11_52") (pintype "bidirectional"))
    )
    (net (code "22") (name "C3") (class "Default")
      (node (ref "JP2") (pin "4") (pinfunction "4_4") (pintype "passive"))
      (node (ref "U3") (pin "51") (pinfunction "PC10_51") (pintype "bidirectional"))
    )
    (net (code "23") (name "C4") (class "Default")
      (node (ref "JP2") (pin "5") (pinfunction "5_5") (pintype "passive"))
      (node (ref "U3") (pin "62") (pinfunction "PB9_62") (pintype "bidirectional"))
    )
    (net (code "24") (name "C5") (class "Default")
      (node (ref "JP2") (pin "6") (pinfunction "6_6") (pintype "passive"))
      (node (ref "U3") (pin "61") (pinfunction "PB8_61") (pintype "bidirectional"))
    )
    (net (code "25") (name "CTS_UB") (class "Default")
      (node (ref "R31") (pin "1") (pinfunction "1_1") (pintype "passive"))
      (node (ref "U1") (pin "11") (pinfunction "CTS_11") (pintype "bidirectional"))
      (node (ref "U8") (pin "15") (pinfunction "1B1_15") (pintype "bidirectional"))
    )
    (net (code "26") (name "CTS_UC") (class "Default")
      (node (ref "U3") (pin "34") (pinfunction "PB13_34") (pintype "bidirectional"))
      (node (ref "U8") (pin "6") (pinfunction "1A1_6") (pintype "bidirectional"))
    )
    (net (code "27") (name "D0") (class "Default")
      (node (ref "JP2") (pin "7") (pinfunction "7_7") (pintype "passive"))
      (node (ref "U3") (pin "59") (pinfunction "PB7_59") (pintype "bidirectional"))
    )
    (net (code "28") (name "D1") (class "Default")
      (node (ref "JP2") (pin "8") (pinfunction "8_8") (pintype "passive"))
      (node (ref "U3") (pin "58") (pinfunction "PB6_58") (pintype "bidirectional"))
    )
    (net (code "29") (name "D2") (class "Default")
      (node (ref "JP2") (pin "9") (pinfunction "9_9") (pintype "passive"))
      (node (ref "U3") (pin "57") (pinfunction "PB5_57") (pintype "bidirectional"))
    )
    (net (code "30") (name "D3") (class "Default")
      (node (ref "JP2") (pin "10") (pinfunction "10_10") (pintype "passive"))
      (node (ref "U3") (pin "56") (pinfunction "NJTRST/PB4_56") (pintype "bidirectional"))
    )
    (net (code "31") (name "D4") (class "Default")
      (node (ref "JP2") (pin "11") (pinfunction "11_11") (pintype "passive"))
      (node (ref "U3") (pin "55") (pinfunction "JTDO/TRACESSW0/PB3_55") (pintype "bidirectional"))
    )
    (net (code "32") (name "D5") (class "Default")
      (node (ref "JP2") (pin "12") (pinfunction "12_12") (pintype "passive"))
      (node (ref "U3") (pin "50") (pinfunction "JTDI/PA15_50") (pintype "bidirectional"))
    )
    (net (code "33") (name "D6") (class "Default")
      (node (ref "JP2") (pin "13") (pinfunction "13_13") (pintype "passive"))
      (node (ref "U3") (pin "49") (pinfunction "JTCK/SWCLK/PA14_49") (pintype "bidirectional"))
    )
    (net (code "34") (name "D7") (class "Default")
      (node (ref "JP2") (pin "14") (pinfunction "14_14") (pintype "passive"))
      (node (ref "R10") (pin "2") (pinfunction "2_2") (pintype "passive"))
      (node (ref "U3") (pin "46") (pinfunction "JTMS/SWDIO/PA13_46") (pintype "bidirectional"))
    )
    (net (code "35") (name "DSEL_PP") (class "Default")
      (node (ref "R7") (pin "2") (pinfunction "2_2") (pintype "passive"))
      (node (ref "U$10") (pin "P$20") (pinfunction "DSEL_P$20") (pintype "bidirectional"))
    )
    (net (code "36") (name "DTR_UB") (class "Default")
      (node (ref "R3") (pin "1") (pinfunction "1_1") (pintype "passive"))
      (node (ref "U1") (pin "9") (pinfunction "DTR_9") (pintype "bidirectional"))
      (node (ref "U2") (pin "13") (pinfunction "2B1_13") (pintype "bidirectional"))
    )
    (net (code "37") (name "DTR_UC") (class "Default")
      (node (ref "R27") (pin "1") (pinfunction "1_1") (pintype "passive"))
      (node (ref "U2") (pin "8") (pinfunction "2A1_8") (pintype "bidirectional"))
      (node (ref "U3") (pin "36") (pinfunction "PB15_36") (pintype "bidirectional"))
      (node (ref "U9") (pin "4") (pinfunction "ON_4") (pintype "input"))
    )
    (net (code "38") (name "GND") (class "Default")
      (node (ref "BLUE_LED_0603") (pin "C") (pinfunction "C_C") (pintype "passive"))
      (node (ref "C1") (pin "2") (pinfunction "2_2") (pintype "passive"))
      (node (ref "C10") (pin "2") (pinfunction "2_2") (pintype "passive"))
      (node (ref "C11") (pin "2") (pinfunction "2_2") (pintype "passive"))
      (node (ref "C12") (pin "2") (pinfunction "2_2") (pintype "passive"))
      (node (ref "C13") (pin "2") (pinfunction "2_2") (pintype "passive"))
      (node (ref "C14") (pin "2") (pinfunction "2_2") (pintype "passive"))
      (node (ref "C15") (pin "2") (pinfunction "2_2") (pintype "passive"))
      (node (ref "C16") (pin "2") (pinfunction "2_2") (pintype "passive"))
      (node (ref "C17") (pin "2") (pinfunction "2_2") (pintype "passive"))
      (node (ref "C18") (pin "2") (pinfunction "2_2") (pintype "passive"))
      (node (ref "C19") (pin "2") (pinfunction "2_2") (pintype "passive"))
      (node (ref "C2") (pin "2") (pinfunction "2_2") (pintype "passive"))
      (node (ref "C20") (pin "2") (pinfunction "2_2") (pintype "passive"))
      (node (ref "C21") (pin "2") (pinfunction "2_2") (pintype "passive"))
      (node (ref "C22") (pin "2") (pinfunction "2_2") (pintype "passive"))
      (node (ref "C23") (pin "2") (pinfunction "2_2") (pintype "passive"))
      (node (ref "C24") (pin "2") (pinfunction "2_2") (pintype "passive"))
      (node (ref "C25") (pin "2") (pinfunction "2_2") (pintype "passive"))
      (node (ref "C26") (pin "2") (pinfunction "2_2") (pintype "passive"))
      (node (ref "C27") (pin "2") (pinfunction "2_2") (pintype "passive"))
      (node (ref "C28") (pin "2") (pinfunction "2_2") (pintype "passive"))
      (node (ref "C29") (pin "2") (pinfunction "2_2") (pintype "passive"))
      (node (ref "C3") (pin "-") (pinfunction "-_-") (pintype "passive"))
      (node (ref "C30") (pin "2") (pinfunction "2_2") (pintype "passive"))
      (node (ref "C31") (pin "2") (pinfunction "2_2") (pintype "passive"))
      (node (ref "C32") (pin "2") (pinfunction "2_2") (pintype "passive"))
      (node (ref "C33") (pin "2") (pinfunction "2_2") (pintype "passive"))
      (node (ref "C34") (pin "2") (pinfunction "2_2") (pintype "passive"))
      (node (ref "C35") (pin "2") (pinfunction "2_2") (pintype "passive"))
      (node (ref "C36") (pin "2") (pinfunction "2_2") (pintype "passive"))
      (node (ref "C37") (pin "2") (pinfunction "2_2") (pintype "passive"))
      (node (ref "C38") (pin "2") (pinfunction "2_2") (pintype "passive"))
      (node (ref "C39") (pin "2") (pinfunction "2_2") (pintype "passive"))
      (node (ref "C4") (pin "2") (pinfunction "2_2") (pintype "passive"))
      (node (ref "C40") (pin "2") (pinfunction "2_2") (pintype "passive"))
      (node (ref "C41") (pin "2") (pinfunction "2_2") (pintype "passive"))
      (node (ref "C42") (pin "2") (pinfunction "2_2") (pintype "passive"))
      (node (ref "C5") (pin "2") (pinfunction "2_2") (pintype "passive"))
      (node (ref "C6") (pin "2") (pinfunction "2_2") (pintype "passive"))
      (node (ref "C8") (pin "2") (pinfunction "2_2") (pintype "passive"))
      (node (ref "C9") (pin "2") (pinfunction "2_2") (pintype "passive"))
      (node (ref "J1") (pin "C5") (pinfunction "GND_C5") (pintype "passive"))
      (node (ref "J2") (pin "2@1") (pinfunction "GND_2@1") (pintype "passive"))
      (node (ref "J2") (pin "2@2") (pinfunction "GND_2@2") (pintype "passive"))
      (node (ref "JP1") (pin "2") (pinfunction "2_2") (pintype "passive"))
      (node (ref "JP2") (pin "15") (pinfunction "15_15") (pintype "passive"))
      (node (ref "JP4") (pin "GND") (pinfunction "1_GND") (pintype "passive"))
      (node (ref "R17") (pin "2") (pinfunction "2_2") (pintype "passive"))
      (node (ref "R19") (pin "2") (pinfunction "2_2") (pintype "passive"))
      (node (ref "R2") (pin "2") (pinfunction "2_2") (pintype "passive"))
      (node (ref "R21") (pin "2") (pinfunction "2_2") (pintype "passive"))
      (node (ref "R24") (pin "2") (pinfunction "2_2") (pintype "passive"))
      (node (ref "R25") (pin "2") (pinfunction "2_2") (pintype "passive"))
      (node (ref "R28") (pin "2") (pinfunction "2_2") (pintype "passive"))
      (node (ref "R31") (pin "2") (pinfunction "2_2") (pintype "passive"))
      (node (ref "RESET") (pin "3") (pinfunction "3_3") (pintype "passive"))
      (node (ref "RESET") (pin "4") (pinfunction "4_4") (pintype "passive"))
      (node (ref "SETUP") (pin "1") (pinfunction "1_1") (pintype "passive"))
      (node (ref "SETUP") (pin "2") (pinfunction "2_2") (pintype "passive"))
      (node (ref "U$1") (pin "17") (pinfunction "PGND_17") (pintype "passive"))
      (node (ref "U$1") (pin "18") (pinfunction "PGND_18") (pintype "passive"))
      (node (ref "U$1") (pin "PAD") (pinfunction "PAD_PAD") (pintype "power_in"))
      (node (ref "U$1") (pin "PAD@1") (pinfunction "PAD_PAD@1") (pintype "power_in"))
      (node (ref "U$1") (pin "PAD@2") (pinfunction "PAD_PAD@2") (pintype "power_in"))
      (node (ref "U$1") (pin "PAD@3") (pinfunction "PAD_PAD@3") (pintype "power_in"))
      (node (ref "U$1") (pin "PAD@4") (pinfunction "PAD_PAD@4") (pintype "power_in"))
      (node (ref "U$1") (pin "PAD@5") (pinfunction "PAD_PAD@5") (pintype "power_in"))
      (node (ref "U$1") (pin "PAD@6") (pinfunction "PAD_PAD@6") (pintype "power_in"))
      (node (ref "U$1") (pin "PAD@7") (pinfunction "PAD_PAD@7") (pintype "power_in"))
      (node (ref "U$1") (pin "PAD@8") (pinfunction "PAD_PAD@8") (pintype "power_in"))
      (node (ref "U$1") (pin "PAD@9") (pinfunction "PAD_PAD@9") (pintype "power_in"))
      (node (ref "U$10") (pin "P$10") (pinfunction "GND2_P$10") (pintype "bidirectional"))
      (node (ref "U$10") (pin "P$11") (pinfunction "GND3_P$11") (pintype "bidirectional"))
      (node (ref "U$10") (pin "P$12") (pinfunction "GND4_P$12") (pintype "bidirectional"))
      (node (ref "U$10") (pin "P$13") (pinfunction "GND5_P$13") (pintype "bidirectional"))
      (node (ref "U$10") (pin "P$14") (pinfunction "GND6_P$14") (pintype "bidirectional"))
      (node (ref "U$10") (pin "P$15") (pinfunction "GND7_P$15") (pintype "bidirectional"))
      (node (ref "U$10") (pin "P$18") (pinfunction "GND8_P$18") (pintype "bidirectional"))
      (node (ref "U$10") (pin "P$19") (pinfunction "GND9_P$19") (pintype "bidirectional"))
      (node (ref "U$10") (pin "P$21") (pinfunction "GND10_P$21") (pintype "bidirectional"))
      (node (ref "U$10") (pin "P$22") (pinfunction "GND11_P$22") (pintype "bidirectional"))
      (node (ref "U$10") (pin "P$27") (pinfunction "GND12_P$27") (pintype "bidirectional"))
      (node (ref "U$10") (pin "P$31") (pinfunction "GND13_P$31") (pintype "bidirectional"))
      (node (ref "U$10") (pin "P$4") (pinfunction "GND_P$4") (pintype "bidirectional"))
      (node (ref "U$10") (pin "P$5") (pinfunction "GND1_P$5") (pintype "bidirectional"))
      (node (ref "U$5") (pin "P$2") (pinfunction "P$2_P$2") (pintype "bidirectional"))
      (node (ref "U$5") (pin "P$6") (pinfunction "P$6_P$6") (pintype "bidirectional"))
      (node (ref "U$5") (pin "TP") (pinfunction "P$6_TP") (pintype "bidirectional"))
      (node (ref "U1") (pin "1") (pinfunction "GND_1") (pintype "bidirectional"))
      (node (ref "U1") (pin "14") (pinfunction "GND_14") (pintype "bidirectional"))
      (node (ref "U1") (pin "20") (pinfunction "GND_20") (pintype "bidirectional"))
      (node (ref "U1") (pin "21") (pinfunction "GND_21") (pintype "bidirectional"))
      (node (ref "U1") (pin "22") (pinfunction "GND_22") (pintype "bidirectional"))
      (node (ref "U1") (pin "3") (pinfunction "GND_3") (pintype "bidirectional"))
      (node (ref "U1") (pin "30") (pinfunction "GND_30") (pintype "bidirectional"))
      (node (ref "U1") (pin "32") (pinfunction "GND65...96_32") (pintype "bidirectional"))
      (node (ref "U1") (pin "33") (pinfunction "RSVD_33") (pintype "bidirectional"))
      (node (ref "U1") (pin "43") (pinfunction "GND_43") (pintype "bidirectional"))
      (node (ref "U1") (pin "5") (pinfunction "GND_5") (pintype "bidirectional"))
      (node (ref "U1") (pin "50") (pinfunction "GND_50") (pintype "bidirectional"))
      (node (ref "U1") (pin "54") (pinfunction "GND_54") (pintype "bidirectional"))
      (node (ref "U1") (pin "55") (pinfunction "GND_55") (pintype "bidirectional"))
      (node (ref "U1") (pin "57") (pinfunction "GND_57") (pintype "bidirectional"))
      (node (ref "U1") (pin "58") (pinfunction "GND_58") (pintype "bidirectional"))
      (node (ref "U1") (pin "59") (pinfunction "GND_59") (pintype "bidirectional"))
      (node (ref "U1") (pin "60") (pinfunction "GND_60") (pintype "bidirectional"))
      (node (ref "U1") (pin "61") (pinfunction "GND_61") (pintype "bidirectional"))
      (node (ref "U1") (pin "63") (pinfunction "GND_63") (pintype "bidirectional"))
      (node (ref "U1") (pin "64") (pinfunction "GND_64") (pintype "bidirectional"))
      (node (ref "U1") (pin "65") (pinfunction "GND65...96_65") (pintype "bidirectional"))
      (node (ref "U1") (pin "66") (pinfunction "GND65...96_66") (pintype "bidirectional"))
      (node (ref "U1") (pin "67") (pinfunction "GND65...96_67") (pintype "bidirectional"))
      (node (ref "U1") (pin "68") (pinfunction "GND65...96_68") (pintype "bidirectional"))
      (node (ref "U1") (pin "69") (pinfunction "GND65...96_69") (pintype "bidirectional"))
      (node (ref "U1") (pin "70") (pinfunction "GND65...96_70") (pintype "bidirectional"))
      (node (ref "U1") (pin "71") (pinfunction "GND65...96_71") (pintype "bidirectional"))
      (node (ref "U1") (pin "72") (pinfunction "GND65...96_72") (pintype "bidirectional"))
      (node (ref "U1") (pin "73") (pinfunction "GND65...96_73") (pintype "bidirectional"))
      (node (ref "U1") (pin "74") (pinfunction "GND65...96_74") (pintype "bidirectional"))
      (node (ref "U1") (pin "75") (pinfunction "GND65...96_75") (pintype "bidirectional"))
      (node (ref "U1") (pin "76") (pinfunction "GND65...96_76") (pintype "bidirectional"))
      (node (ref "U1") (pin "77") (pinfunction "GND65...96_77") (pintype "bidirectional"))
      (node (ref "U1") (pin "78") (pinfunction "GND65...96_78") (pintype "bidirectional"))
      (node (ref "U1") (pin "79") (pinfunction "GND65...96_79") (pintype "bidirectional"))
      (node (ref "U1") (pin "80") (pinfunction "GND65...96_80") (pintype "bidirectional"))
      (node (ref "U1") (pin "81") (pinfunction "GND65...96_81") (pintype "bidirectional"))
      (node (ref "U1") (pin "82") (pinfunction "GND65...96_82") (pintype "bidirectional"))
      (node (ref "U1") (pin "83") (pinfunction "GND65...96_83") (pintype "bidirectional"))
      (node (ref "U1") (pin "84") (pinfunction "GND65...96_84") (pintype "bidirectional"))
      (node (ref "U1") (pin "85") (pinfunction "GND65...96_85") (pintype "bidirectional"))
      (node (ref "U1") (pin "86") (pinfunction "GND65...96_86") (pintype "bidirectional"))
      (node (ref "U1") (pin "87") (pinfunction "GND65...96_87") (pintype "bidirectional"))
      (node (ref "U1") (pin "88") (pinfunction "GND65...96_88") (pintype "bidirectional"))
      (node (ref "U1") (pin "89") (pinfunction "GND65...96_89") (pintype "bidirectional"))
      (node (ref "U1") (pin "90") (pinfunction "GND65...96_90") (pintype "bidirectional"))
      (node (ref "U1") (pin "91") (pinfunction "GND65...96_91") (pintype "bidirectional"))
      (node (ref "U1") (pin "92") (pinfunction "GND65...96_92") (pintype "bidirectional"))
      (node (ref "U1") (pin "93") (pinfunction "GND65...96_93") (pintype "bidirectional"))
      (node (ref "U1") (pin "94") (pinfunction "GND65...96_94") (pintype "bidirectional"))
      (node (ref "U1") (pin "95") (pinfunction "GND65...96_95") (pintype "bidirectional"))
      (node (ref "U1") (pin "96") (pinfunction "GND65...96_96") (pintype "bidirectional"))
      (node (ref "U2") (pin "1") (pinfunction "1/OE_1") (pintype "bidirectional"))
      (node (ref "U2") (pin "10") (pinfunction "GND_10") (pintype "bidirectional"))
      (node (ref "U2") (pin "11") (pinfunction "GND_11") (pintype "bidirectional"))
      (node (ref "U2") (pin "16") (pinfunction "2/OE_16") (pintype "bidirectional"))
      (node (ref "U2") (pin "9") (pinfunction "2A2_9") (pintype "bidirectional"))
      (node (ref "U3") (pin "12") (pinfunction "VSSA_12") (pintype "power_in"))
      (node (ref "U3") (pin "18") (pinfunction "VSS_4_18") (pintype "power_in"))
      (node (ref "U3") (pin "60") (pinfunction "BOOT0_60") (pintype "bidirectional"))
      (node (ref "U3") (pin "63") (pinfunction "VSS_3_63") (pintype "power_in"))
      (node (ref "U4") (pin "1") (pinfunction "CTG_1") (pintype "bidirectional"))
      (node (ref "U4") (pin "4") (pinfunction "GND_4") (pintype "bidirectional"))
      (node (ref "U4") (pin "6") (pinfunction "QST_6") (pintype "bidirectional"))
      (node (ref "U4") (pin "EP") (pinfunction "GND_EP") (pintype "bidirectional"))
      (node (ref "U5") (pin "3") (pinfunction "GND_3") (pintype "bidirectional"))
      (node (ref "U6") (pin "3") (pinfunction "GND_3") (pintype "bidirectional"))
      (node (ref "U8") (pin "1") (pinfunction "1/OE_1") (pintype "bidirectional"))
      (node (ref "U8") (pin "10") (pinfunction "GND_10") (pintype "bidirectional"))
      (node (ref "U8") (pin "11") (pinfunction "GND_11") (pintype "bidirectional"))
      (node (ref "U8") (pin "12") (pinfunction "2B2_12") (pintype "bidirectional"))
      (node (ref "U8") (pin "16") (pinfunction "2/OE_16") (pintype "bidirectional"))
      (node (ref "U8") (pin "4") (pinfunction "1DIR_4") (pintype "bidirectional"))
      (node (ref "U8") (pin "5") (pinfunction "2DIR_5") (pintype "bidirectional"))
      (node (ref "U9") (pin "2") (pinfunction "GND_2") (pintype "passive"))
      (node (ref "X1") (pin "GND") (pinfunction "GND_GND") (pintype "bidirectional"))
      (node (ref "X1") (pin "MT1") (pinfunction "GND_MT1") (pintype "bidirectional"))
      (node (ref "X1") (pin "MT2") (pinfunction "GND_MT2") (pintype "bidirectional"))
    )
    (net (code "39") (name "ILIM") (class "Default")
      (node (ref "R2") (pin "1") (pinfunction "1_1") (pintype "passive"))
      (node (ref "U$1") (pin "10") (pinfunction "ILIM_10") (pintype "output"))
    )
    (net (code "40") (name "LED1") (class "Default")
      (node (ref "BLUE_LED_0603") (pin "A") (pinfunction "A_A") (pintype "passive"))
      (node (ref "R10") (pin "1") (pinfunction "1_1") (pintype "passive"))
    )
    (net (code "41") (name "Net-(LED2-2)") (class "Default")
      (node (ref "LED2") (pin "BLUE") (pinfunction "2_BLUE") (pintype "passive"))
      (node (ref "R11") (pin "1") (pinfunction "1_1") (pintype "passive"))
    )
    (net (code "42") (name "Net-(LED2-3)") (class "Default")
      (node (ref "LED2") (pin "GREEN") (pinfunction "3_GREEN") (pintype "passive"))
      (node (ref "R9") (pin "1") (pinfunction "1_1") (pintype "passive"))
    )
    (net (code "43") (name "Net-(LED2-4)") (class "Default")
      (node (ref "LED2") (pin "RED") (pinfunction "4_RED") (pintype "passive"))
      (node (ref "R12") (pin "1") (pinfunction "1_1") (pintype "passive"))
    )
    (net (code "44") (name "Net-(R4-Pad2)") (class "Default")
      (node (ref "R4") (pin "2") (pinfunction "2_2") (pintype "passive"))
      (node (ref "RED_LED_0603") (pin "C") (pinfunction "C_C") (pintype "passive"))
    )
    (net (code "45") (name "Net-(U$1-OTG)") (class "Default")
      (node (ref "R16") (pin "1") (pinfunction "1_1") (pintype "passive"))
      (node (ref "U$1") (pin "8") (pinfunction "OTG_8") (pintype "bidirectional"))
    )
    (net (code "46") (name "Net-(U$1-TS)") (class "Default")
      (node (ref "R18") (pin "2") (pinfunction "2_2") (pintype "passive"))
      (node (ref "R19") (pin "1") (pinfunction "1_1") (pintype "passive"))
      (node (ref "U$1") (pin "11") (pinfunction "TS_11") (pintype "bidirectional"))
      (node (ref "U$1") (pin "12") (pinfunction "~{QON}_12") (pintype "bidirectional"))
    )
    (net (code "47") (name "Net-(U3-VCAP_1)") (class "Default")
      (node (ref "C35") (pin "1") (pinfunction "1_1") (pintype "passive"))
      (node (ref "U3") (pin "31") (pinfunction "VCAP_1_31") (pintype "power_in"))
    )
    (net (code "48") (name "Net-(U3-VCAP_2)") (class "Default")
      (node (ref "C32") (pin "1") (pinfunction "1_1") (pintype "passive"))
      (node (ref "U3") (pin "47") (pinfunction "VCAP_2_47") (pintype "power_in"))
    )
    (net (code "49") (name "Net-(U4-CELL)") (class "Default")
      (node (ref "C39") (pin "1") (pinfunction "1_1") (pintype "passive"))
      (node (ref "R23") (pin "1") (pinfunction "1_1") (pintype "passive"))
      (node (ref "U4") (pin "2") (pinfunction "CELL_2") (pintype "bidirectional"))
    )
    (net (code "50") (name "Net-(U4-VDD)") (class "Default")
      (node (ref "C38") (pin "1") (pinfunction "1_1") (pintype "passive"))
      (node (ref "R22") (pin "1") (pinfunction "1_1") (pintype "passive"))
      (node (ref "U4") (pin "3") (pinfunction "VDD_3") (pintype "bidirectional"))
    )
    (net (code "51") (name "OSC32_IN_UC") (class "Default")
      (node (ref "C34") (pin "1") (pinfunction "1_1") (pintype "passive"))
      (node (ref "U3") (pin "3") (pinfunction "PC14_3") (pintype "bidirectional"))
      (node (ref "Y1") (pin "X1") (pinfunction "1_X1") (pintype "passive"))
    )
    (net (code "52") (name "OSC32_OUT_UC") (class "Default")
      (node (ref "C33") (pin "1") (pinfunction "1_1") (pintype "passive"))
      (node (ref "U3") (pin "4") (pinfunction "PC15_4") (pintype "bidirectional"))
      (node (ref "Y1") (pin "X2") (pinfunction "2_X2") (pintype "passive"))
    )
    (net (code "53") (name "OSC_IN_UC") (class "Default")
      (node (ref "C28") (pin "1") (pinfunction "1_1") (pintype "passive"))
      (node (ref "U3") (pin "5") (pinfunction "PH0/OSC_IN_5") (pintype "bidirectional"))
      (node (ref "Y2") (pin "1") (pinfunction "1_1") (pintype "passive"))
    )
    (net (code "54") (name "OSC_OUT_UC") (class "Default")
      (node (ref "C26") (pin "1") (pinfunction "1_1") (pintype "passive"))
      (node (ref "U3") (pin "6") (pinfunction "PH1/OSC_OUT_6") (pintype "bidirectional"))
      (node (ref "Y2") (pin "3") (pinfunction "2_3") (pintype "passive"))
    )
    (net (code "55") (name "PA8_PM_SCL") (class "Default")
      (node (ref "R14") (pin "1") (pinfunction "1_1") (pintype "passive"))
      (node (ref "U$1") (pin "5") (pinfunction "SCL_5") (pintype "output"))
      (node (ref "U$9") (pin "P$1") (pinfunction "TP_P$1") (pintype "bidirectional"))
      (node (ref "U3") (pin "41") (pinfunction "PA8_41") (pintype "bidirectional"))
      (node (ref "U4") (pin "7") (pinfunction "SCL_7") (pintype "bidirectional"))
    )
    (net (code "56") (name "PC9_PM_SDA") (class "Default")
      (node (ref "R13") (pin "1") (pinfunction "1_1") (pintype "passive"))
      (node (ref "U$1") (pin "6") (pinfunction "SDA_6") (pintype "bidirectional"))
      (node (ref "U$8") (pin "P$1") (pinfunction "TP_P$1") (pintype "bidirectional"))
      (node (ref "U3") (pin "40") (pinfunction "PC9_40") (pintype "bidirectional"))
      (node (ref "U4") (pin "8") (pinfunction "SDA_8") (pintype "bidirectional"))
    )
    (net (code "57") (name "PMID") (class "Default")
      (node (ref "C5") (pin "1") (pinfunction "1_1") (pintype "passive"))
      (node (ref "U$1") (pin "23") (pinfunction "PMID_23") (pintype "passive"))
    )
    (net (code "58") (name "PWR_UB") (class "Default")
      (node (ref "R1") (pin "1") (pinfunction "1_1") (pintype "passive"))
      (node (ref "U1") (pin "15") (pinfunction "PWR_ON_15") (pintype "bidirectional"))
      (node (ref "U5") (pin "4") (pinfunction "B_4") (pintype "bidirectional"))
    )
    (net (code "59") (name "PWR_UC") (class "Default")
      (node (ref "R29") (pin "1") (pinfunction "1_1") (pintype "passive"))
      (node (ref "U3") (pin "28") (pinfunction "PB2_28") (pintype "bidirectional"))
      (node (ref "U5") (pin "2") (pinfunction "A_2") (pintype "bidirectional"))
    )
    (net (code "60") (name "P_3V3") (class "Default")
      (node (ref "C18") (pin "1") (pinfunction "1_1") (pintype "passive"))
      (node (ref "C19") (pin "1") (pinfunction "1_1") (pintype "passive"))
      (node (ref "U2") (pin "3") (pinfunction "VCCA_3") (pintype "bidirectional"))
      (node (ref "U2") (pin "4") (pinfunction "1DIR_4") (pintype "bidirectional"))
      (node (ref "U2") (pin "5") (pinfunction "2DIR_5") (pintype "bidirectional"))
      (node (ref "U8") (pin "3") (pinfunction "VCCA_3") (pintype "bidirectional"))
      (node (ref "U9") (pin "1") (pinfunction "VOUT_1") (pintype "output"))
    )
    (net (code "61") (name "REGN") (class "Default")
      (node (ref "C25") (pin "1") (pinfunction "1_1") (pintype "passive"))
      (node (ref "R18") (pin "1") (pinfunction "1_1") (pintype "passive"))
      (node (ref "U$1") (pin "22") (pinfunction "REGN_22") (pintype "bidirectional"))
    )
    (net (code "62") (name "RESET_UB") (class "Default")
      (node (ref "U1") (pin "18") (pinfunction "RESET_N_18") (pintype "bidirectional"))
      (node (ref "U6") (pin "4") (pinfunction "B_4") (pintype "bidirectional"))
    )
    (net (code "63") (name "RESET_UC") (class "Default")
      (node (ref "R30") (pin "1") (pinfunction "1_1") (pintype "passive"))
      (node (ref "U3") (pin "24") (pinfunction "PC4_24") (pintype "bidirectional"))
      (node (ref "U6") (pin "2") (pinfunction "A_2") (pintype "bidirectional"))
    )
    (net (code "64") (name "RGB_BLUE") (class "Default")
      (node (ref "R11") (pin "2") (pinfunction "2_2") (pintype "passive"))
      (node (ref "U$13") (pin "P$1") (pinfunction "TP_P$1") (pintype "bidirectional"))
      (node (ref "U3") (pin "17") (pinfunction "PA3_17") (pintype "bidirectional"))
    )
    (net (code "65") (name "RGB_GREEN") (class "Default")
      (node (ref "R9") (pin "2") (pinfunction "2_2") (pintype "passive"))
      (node (ref "U$12") (pin "P$1") (pinfunction "TP_P$1") (pintype "bidirectional"))
      (node (ref "U3") (pin "16") (pinfunction "PA2_16") (pintype "bidirectional"))
    )
    (net (code "66") (name "RGB_RED") (class "Default")
      (node (ref "R12") (pin "2") (pinfunction "2_2") (pintype "passive"))
      (node (ref "U$11") (pin "P$1") (pinfunction "TP_P$1") (pintype "bidirectional"))
      (node (ref "U3") (pin "15") (pinfunction "PA1_15") (pintype "bidirectional"))
    )
    (net (code "67") (name "RI_UB") (class "Default")
      (node (ref "R28") (pin "1") (pinfunction "1_1") (pintype "passive"))
      (node (ref "U1") (pin "7") (pinfunction "RI_7") (pintype "bidirectional"))
      (node (ref "U8") (pin "14") (pinfunction "1B2_14") (pintype "bidirectional"))
    )
    (net (code "68") (name "RI_UC") (class "Default")
      (node (ref "U3") (pin "33") (pinfunction "PB12_33") (pintype "bidirectional"))
      (node (ref "U8") (pin "7") (pinfunction "1A2_7") (pintype "bidirectional"))
    )
    (net (code "69") (name "RTS_UB") (class "Default")
      (node (ref "U1") (pin "10") (pinfunction "RTS_10") (pintype "bidirectional"))
      (node (ref "U2") (pin "15") (pinfunction "1B1_15") (pintype "bidirectional"))
    )
    (net (code "70") (name "RTS_UC") (class "Default")
      (node (ref "R24") (pin "1") (pinfunction "1_1") (pintype "passive"))
      (node (ref "U2") (pin "6") (pinfunction "1A1_6") (pintype "bidirectional"))
      (node (ref "U3") (pin "35") (pinfunction "PB14_35") (pintype "bidirectional"))
    )
    (net (code "71") (name "RX") (class "Default")
      (node (ref "JP1") (pin "4") (pinfunction "4_4") (pintype "passive"))
      (node (ref "U$10") (pin "P$25") (pinfunction "TXD_P$25") (pintype "bidirectional"))
      (node (ref "U3") (pin "43") (pinfunction "PA10_43") (pintype "bidirectional"))
    )
    (net (code "72") (name "RXD_UB") (class "Default")
      (node (ref "R21") (pin "1") (pinfunction "1_1") (pintype "passive"))
      (node (ref "U1") (pin "13") (pinfunction "RXD_13") (pintype "bidirectional"))
      (node (ref "U8") (pin "13") (pinfunction "2B1_13") (pintype "bidirectional"))
    )
    (net (code "73") (name "RXD_UC") (class "Default")
      (node (ref "U3") (pin "30") (pinfunction "PB11_30") (pintype "bidirectional"))
      (node (ref "U8") (pin "8") (pinfunction "2A1_8") (pintype "bidirectional"))
    )
    (net (code "74") (name "SIM_CLK") (class "Default")
      (node (ref "C12") (pin "1") (pinfunction "1_1") (pintype "passive"))
      (node (ref "J1") (pin "C3") (pinfunction "CLK_C3") (pintype "passive"))
      (node (ref "U1") (pin "38") (pinfunction "SIM_CLK_38") (pintype "bidirectional"))
    )
    (net (code "75") (name "SIM_DET") (class "Default")
      (node (ref "U1") (pin "42") (pinfunction "SIM_DET_42") (pintype "bidirectional"))
    )
    (net (code "76") (name "SIM_IO") (class "Default")
      (node (ref "C13") (pin "1") (pinfunction "1_1") (pintype "passive"))
      (node (ref "J1") (pin "C7") (pinfunction "I/O_C7") (pintype "passive"))
      (node (ref "U1") (pin "39") (pinfunction "SIM_IO_39") (pintype "bidirectional"))
    )
    (net (code "77") (name "SIM_RST") (class "Default")
      (node (ref "C10") (pin "1") (pinfunction "1_1") (pintype "passive"))
      (node (ref "J1") (pin "C2") (pinfunction "RST_C2") (pintype "passive"))
      (node (ref "U1") (pin "40") (pinfunction "SIM_RST_40") (pintype "bidirectional"))
    )
    (net (code "78") (name "SIM_VCC") (class "Default")
      (node (ref "C11") (pin "1") (pinfunction "1_1") (pintype "passive"))
      (node (ref "C14") (pin "1") (pinfunction "1_1") (pintype "passive"))
      (node (ref "J1") (pin "C1") (pinfunction "VCC_C1") (pintype "passive"))
      (node (ref "J1") (pin "C6") (pinfunction "VPP_C6") (pintype "passive"))
      (node (ref "U1") (pin "41") (pinfunction "VSIM_41") (pintype "bidirectional"))
    )
    (net (code "79") (name "STAT") (class "Default")
      (node (ref "R4") (pin "1") (pinfunction "1_1") (pintype "passive"))
      (node (ref "U$1") (pin "4") (pinfunction "STAT_4") (pintype "bidirectional"))
    )
    (net (code "80") (name "SW1") (class "Default")
      (node (ref "C7") (pin "2") (pinfunction "2_2") (pintype "passive"))
      (node (ref "U$1") (pin "19") (pinfunction "SW_19") (pintype "power_in"))
      (node (ref "U$1") (pin "20") (pinfunction "SW_20") (pintype "power_in"))
      (node (ref "U$4") (pin "P$1") (pinfunction "1_P$1") (pintype "passive"))
    )
    (net (code "81") (name "SW2") (class "Default")
      (node (ref "U$5") (pin "P$1") (pinfunction "P$1_P$1") (pintype "bidirectional"))
      (node (ref "U$6") (pin "1") (pinfunction "1_1") (pintype "passive"))
    )
    (net (code "82") (name "TST") (class "Default")
      (node (ref "JP1") (pin "6") (pinfunction "6_6") (pintype "passive"))
      (node (ref "U3") (pin "20") (pinfunction "PA4_20") (pintype "bidirectional"))
    )
    (net (code "83") (name "TX") (class "Default")
      (node (ref "JP1") (pin "3") (pinfunction "3_3") (pintype "passive"))
      (node (ref "U$10") (pin "P$26") (pinfunction "RXD_P$26") (pintype "bidirectional"))
      (node (ref "U3") (pin "42") (pinfunction "PA9_42") (pintype "bidirectional"))
    )
    (net (code "84") (name "TXD_UB") (class "Default")
      (node (ref "U1") (pin "12") (pinfunction "TXD_12") (pintype "bidirectional"))
      (node (ref "U2") (pin "14") (pinfunction "1B2_14") (pintype "bidirectional"))
    )
    (net (code "85") (name "TXD_UC") (class "Default")
      (node (ref "R25") (pin "1") (pinfunction "1_1") (pintype "passive"))
      (node (ref "U2") (pin "7") (pinfunction "1A2_7") (pintype "bidirectional"))
      (node (ref "U3") (pin "29") (pinfunction "PB10_29") (pintype "bidirectional"))
    )
    (net (code "86") (name "USB_DM") (class "Default")
      (node (ref "R6") (pin "2") (pinfunction "2_2") (pintype "passive"))
      (node (ref "U$1") (pin "3") (pinfunction "~{PG}_3") (pintype "output"))
      (node (ref "U$7") (pin "P$2") (pinfunction "P$2_P$2") (pintype "bidirectional"))
      (node (ref "X1") (pin "D-") (pinfunction "D-_D-") (pintype "bidirectional"))
    )
    (net (code "87") (name "USB_DM_UC") (class "Default")
      (node (ref "R6") (pin "1") (pinfunction "1_1") (pintype "passive"))
      (node (ref "U3") (pin "44") (pinfunction "PA11_44") (pintype "bidirectional"))
    )
    (net (code "88") (name "USB_DP") (class "Default")
      (node (ref "R5") (pin "2") (pinfunction "2_2") (pintype "passive"))
      (node (ref "U$1") (pin "2") (pinfunction "PSEL_2") (pintype "output"))
      (node (ref "U$7") (pin "P$1") (pinfunction "P$1_P$1") (pintype "bidirectional"))
      (node (ref "X1") (pin "D+") (pinfunction "D+_D+") (pintype "bidirectional"))
    )
    (net (code "89") (name "USB_DP_UC") (class "Default")
      (node (ref "R5") (pin "1") (pinfunction "1_1") (pintype "passive"))
      (node (ref "U3") (pin "45") (pinfunction "PA12_45") (pintype "bidirectional"))
    )
    (net (code "90") (name "VBAT") (class "Default")
      (node (ref "J3") (pin "2") (pinfunction "2_2") (pintype "bidirectional"))
      (node (ref "JP2") (pin "16") (pinfunction "16_16") (pintype "passive"))
      (node (ref "U3") (pin "1") (pinfunction "VBAT_1") (pintype "power_in"))
    )
    (net (code "91") (name "VBUS") (class "Default")
      (node (ref "JP3") (pin "1") (pinfunction "1_1") (pintype "passive"))
      (node (ref "U$3") (pin "ANODE") (pinfunction "ANODE_ANODE") (pintype "bidirectional"))
      (node (ref "X1") (pin "VBUS") (pinfunction "VBUS_VBUS") (pintype "bidirectional"))
    )
    (net (code "92") (name "VIN") (class "Default")
      (node (ref "C4") (pin "1") (pinfunction "1_1") (pintype "passive"))
      (node (ref "JP1") (pin "1") (pinfunction "1_1") (pintype "passive"))
      (node (ref "U$1") (pin "1") (pinfunction "VBUS_1") (pintype "power_in"))
      (node (ref "U$1") (pin "24") (pinfunction "VBUS_24") (pintype "passive"))
      (node (ref "U$3") (pin "CATHODE") (pinfunction "CATHODE_CATHODE") (pintype "bidirectional"))
    )
    (net (code "93") (name "V_BCKP") (class "Default")
      (node (ref "R1") (pin "2") (pinfunction "2_2") (pintype "passive"))
      (node (ref "U1") (pin "2") (pinfunction "V_BCKP_2") (pintype "bidirectional"))
    )
    (net (code "94") (name "V_INT") (class "Default")
      (node (ref "C21") (pin "1") (pinfunction "1_1") (pintype "passive"))
      (node (ref "C22") (pin "1") (pinfunction "1_1") (pintype "passive"))
      (node (ref "R3") (pin "2") (pinfunction "2_2") (pintype "passive"))
      (node (ref "U1") (pin "4") (pinfunction "V_INT_4") (pintype "bidirectional"))
      (node (ref "U2") (pin "2") (pinfunction "VCCB_2") (pintype "bidirectional"))
      (node (ref "U8") (pin "2") (pinfunction "VCCB_2") (pintype "bidirectional"))
    )
    (net (code "95") (name "WKP") (class "Default")
      (node (ref "JP1") (pin "5") (pinfunction "5_5") (pintype "passive"))
      (node (ref "U3") (pin "14") (pinfunction "WKUP/PA0_14") (pintype "bidirectional"))
    )
    (net (code "96") (name "unconnected-(RESET-Pad1)") (class "Default")
      (node (ref "RESET") (pin "1") (pinfunction "1_1") (pintype "passive"))
    )
    (net (code "97") (name "unconnected-(SETUP-Pad4)") (class "Default")
      (node (ref "SETUP") (pin "4") (pinfunction "4_4") (pintype "passive"))
    )
    (net (code "98") (name "unconnected-(U$10-ANT-PadP$16)") (class "Default")
      (node (ref "U$10") (pin "P$16") (pinfunction "ANT_P$16") (pintype "bidirectional"))
    )
    (net (code "99") (name "unconnected-(U$10-ANT_O-PadP$30)") (class "Default")
      (node (ref "U$10") (pin "P$30") (pinfunction "ANT_O_P$30") (pintype "bidirectional"))
    )
    (net (code "100") (name "unconnected-(U$10-EXTINT-PadP$7)") (class "Default")
      (node (ref "U$10") (pin "P$7") (pinfunction "EXTINT_P$7") (pintype "bidirectional"))
    )
    (net (code "101") (name "unconnected-(U$10-RES-PadP$2)") (class "Default")
      (node (ref "U$10") (pin "P$2") (pinfunction "RES_P$2") (pintype "bidirectional"))
    )
    (net (code "102") (name "unconnected-(U$10-RES1-PadP$24)") (class "Default")
      (node (ref "U$10") (pin "P$24") (pinfunction "RES1_P$24") (pintype "bidirectional"))
    )
    (net (code "103") (name "unconnected-(U$10-RES2-PadP$28)") (class "Default")
      (node (ref "U$10") (pin "P$28") (pinfunction "RES2_P$28") (pintype "bidirectional"))
    )
    (net (code "104") (name "unconnected-(U$10-RF_IN-PadP$17)") (class "Default")
      (node (ref "U$10") (pin "P$17") (pinfunction "RF_IN_P$17") (pintype "bidirectional"))
    )
    (net (code "105") (name "unconnected-(U$10-SCL-PadP$6)") (class "Default")
      (node (ref "U$10") (pin "P$6") (pinfunction "SCL_P$6") (pintype "bidirectional"))
    )
    (net (code "106") (name "unconnected-(U$10-SDA-PadP$3)") (class "Default")
      (node (ref "U$10") (pin "P$3") (pinfunction "SDA_P$3") (pintype "bidirectional"))
    )
    (net (code "107") (name "unconnected-(U$10-TIM_PLS-PadP$29)") (class "Default")
      (node (ref "U$10") (pin "P$29") (pinfunction "TIM_PLS_P$29") (pintype "bidirectional"))
    )
    (net (code "108") (name "unconnected-(U1-DCD-Pad8)") (class "Default")
      (node (ref "U1") (pin "8") (pinfunction "DCD_8") (pintype "bidirectional"))
    )
    (net (code "109") (name "unconnected-(U1-DSR-Pad6)") (class "Default")
      (node (ref "U1") (pin "6") (pinfunction "DSR_6") (pintype "bidirectional"))
    )
    (net (code "110") (name "unconnected-(U1-GPIO1-Pad16)") (class "Default")
      (node (ref "U1") (pin "16") (pinfunction "GPIO1_16") (pintype "bidirectional"))
    )
    (net (code "111") (name "unconnected-(U1-GPIO2-Pad23)") (class "Default")
      (node (ref "U1") (pin "23") (pinfunction "GPIO2_23") (pintype "bidirectional"))
    )
    (net (code "112") (name "unconnected-(U1-GPIO3-Pad24)") (class "Default")
      (node (ref "U1") (pin "24") (pinfunction "GPIO3_24") (pintype "bidirectional"))
    )
    (net (code "113") (name "unconnected-(U1-GPIO4-Pad25)") (class "Default")
      (node (ref "U1") (pin "25") (pinfunction "GPIO4_25") (pintype "bidirectional"))
    )
    (net (code "114") (name "unconnected-(U1-I2S_CLK-Pad36)") (class "Default")
      (node (ref "U1") (pin "36") (pinfunction "I2S_CLK_36") (pintype "bidirectional"))
    )
    (net (code "115") (name "unconnected-(U1-I2S_RXD-Pad37)") (class "Default")
      (node (ref "U1") (pin "37") (pinfunction "I2S_RXD_37") (pintype "bidirectional"))
    )
    (net (code "116") (name "unconnected-(U1-I2S_TXD-Pad35)") (class "Default")
      (node (ref "U1") (pin "35") (pinfunction "I2S_TXD_35") (pintype "bidirectional"))
    )
    (net (code "117") (name "unconnected-(U1-I2S_WA-Pad34)") (class "Default")
      (node (ref "U1") (pin "34") (pinfunction "I2S_WA_34") (pintype "bidirectional"))
    )
    (net (code "118") (name "unconnected-(U1-MIC_BIAS-Pad46)") (class "Default")
      (node (ref "U1") (pin "46") (pinfunction "MIC_BIAS_46") (pintype "bidirectional"))
    )
    (net (code "119") (name "unconnected-(U1-MIC_GND-Pad47)") (class "Default")
      (node (ref "U1") (pin "47") (pinfunction "MIC_GND_47") (pintype "bidirectional"))
    )
    (net (code "120") (name "unconnected-(U1-MIC_N-Pad48)") (class "Default")
      (node (ref "U1") (pin "48") (pinfunction "MIC_N_48") (pintype "bidirectional"))
    )
    (net (code "121") (name "unconnected-(U1-MIC_P-Pad49)") (class "Default")
      (node (ref "U1") (pin "49") (pinfunction "MIC_P_49") (pintype "bidirectional"))
    )
    (net (code "122") (name "unconnected-(U1-RSVD-Pad19)") (class "Default")
      (node (ref "U1") (pin "19") (pinfunction "RSVD_19") (pintype "bidirectional"))
    )
    (net (code "123") (name "unconnected-(U1-RSVD-Pad31)") (class "Default")
      (node (ref "U1") (pin "31") (pinfunction "RSVD_31") (pintype "bidirectional"))
    )
    (net (code "124") (name "unconnected-(U1-RXD_AUX{slash}USB_D--Pad28)") (class "Default")
      (node (ref "U1") (pin "28") (pinfunction "RXD_AUX/USB_D-_28") (pintype "bidirectional"))
    )
    (net (code "125") (name "unconnected-(U1-SCL-Pad27)") (class "Default")
      (node (ref "U1") (pin "27") (pinfunction "SCL_27") (pintype "bidirectional"))
    )
    (net (code "126") (name "unconnected-(U1-SDA-Pad26)") (class "Default")
      (node (ref "U1") (pin "26") (pinfunction "SDA_26") (pintype "bidirectional"))
    )
    (net (code "127") (name "unconnected-(U1-SPK_N-Pad45)") (class "Default")
      (node (ref "U1") (pin "45") (pinfunction "SPK_N_45") (pintype "bidirectional"))
    )
    (net (code "128") (name "unconnected-(U1-SPK_P-Pad44)") (class "Default")
      (node (ref "U1") (pin "44") (pinfunction "SPK_P_44") (pintype "bidirectional"))
    )
    (net (code "129") (name "unconnected-(U1-TXD_AUX{slash}USB_D+-Pad29)") (class "Default")
      (node (ref "U1") (pin "29") (pinfunction "TXD_AUX/USB_D+_29") (pintype "bidirectional"))
    )
    (net (code "130") (name "unconnected-(U1-VUSB_DET-Pad17)") (class "Default")
      (node (ref "U1") (pin "17") (pinfunction "VUSB_DET_17") (pintype "bidirectional"))
    )
    (net (code "131") (name "unconnected-(U2-2B2-Pad12)") (class "Default")
      (node (ref "U2") (pin "12") (pinfunction "2B2_12") (pintype "bidirectional"))
    )
    (net (code "132") (name "unconnected-(U8-2A2-Pad9)") (class "Default")
      (node (ref "U8") (pin "9") (pinfunction "2A2_9") (pintype "bidirectional"))
    )
    (net (code "133") (name "unconnected-(U9-OC-Pad3)") (class "Default")
      (node (ref "U9") (pin "3") (pinfunction "OC_3") (pintype "output"))
    )
    (net (code "134") (name "~{BATT_INT_PC13}") (class "Default")
      (node (ref "R15") (pin "1") (pinfunction "1_1") (pintype "passive"))
      (node (ref "U$1") (pin "7") (pinfunction "INT_7") (pintype "bidirectional"))
      (node (ref "U3") (pin "2") (pinfunction "PC13_2") (pintype "bidirectional"))
      (node (ref "U4") (pin "5") (pinfunction "ALT_5") (pintype "bidirectional"))
    )
    (net (code "135") (name "~{CE}") (class "Default")
      (node (ref "R17") (pin "1") (pinfunction "1_1") (pintype "passive"))
      (node (ref "U$1") (pin "9") (pinfunction "~{CE}_9") (pintype "output"))
    )
    (net (code "136") (name "~{RST}") (class "Default")
      (node (ref "C6") (pin "1") (pinfunction "1_1") (pintype "passive"))
      (node (ref "JP2") (pin "17") (pinfunction "17_17") (pintype "passive"))
      (node (ref "R8") (pin "1") (pinfunction "1_1") (pintype "passive"))
      (node (ref "RESET") (pin "2") (pinfunction "2_2") (pintype "passive"))
      (node (ref "U3") (pin "7") (pinfunction "NRST_7") (pintype "power_in"))
    )
    (net (code "137") (name "~{SETUP}") (class "Default")
      (node (ref "SETUP") (pin "3") (pinfunction "3_3") (pintype "passive"))
      (node (ref "U3") (pin "38") (pinfunction "PC7_38") (pintype "bidirectional"))
    )
  )
)
